# transponder-10_5_0.net
KiCad netlist of a schematic drawn in EAGLE
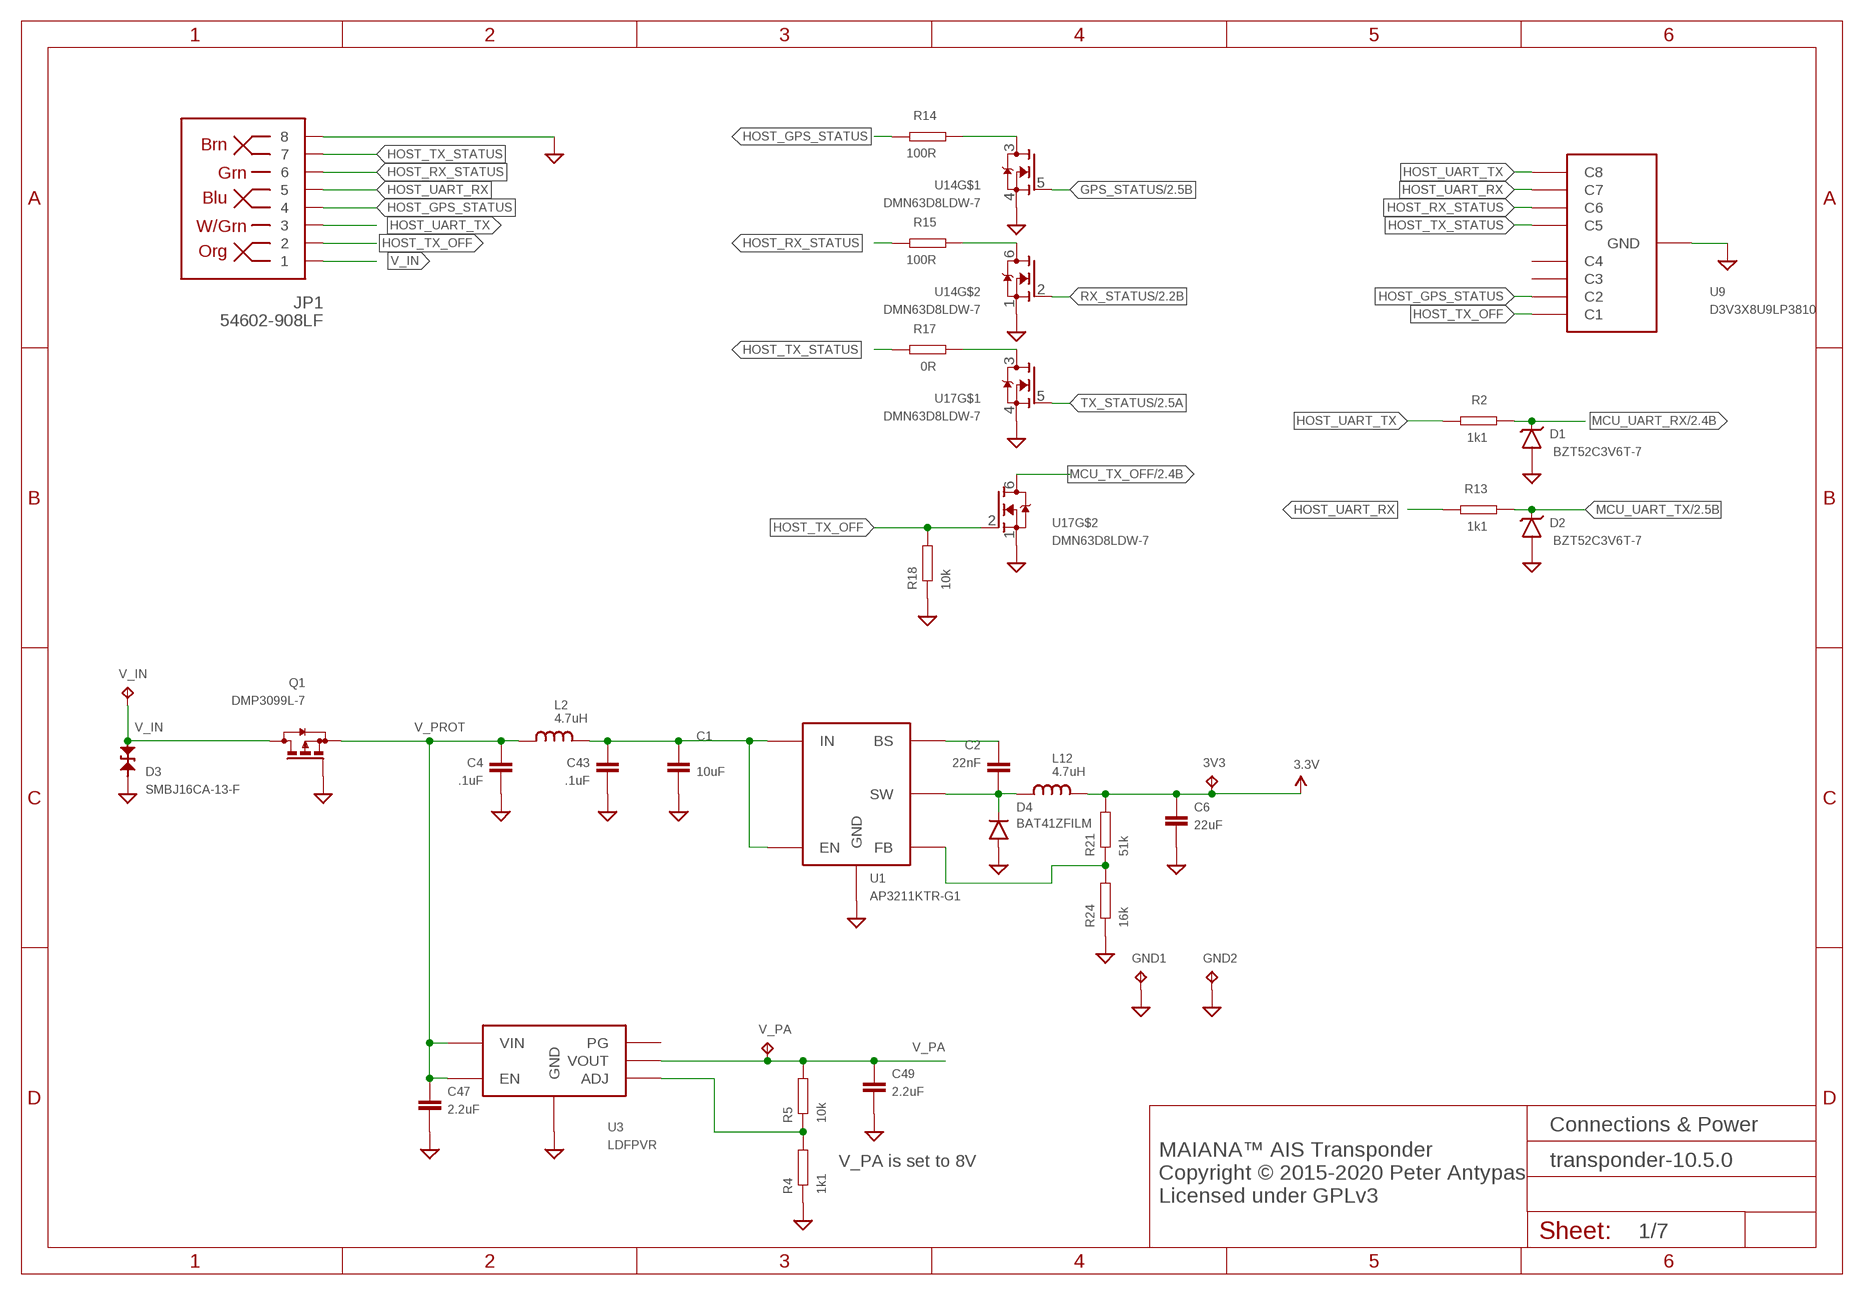
[diagram p0: schematic, sheet 1]
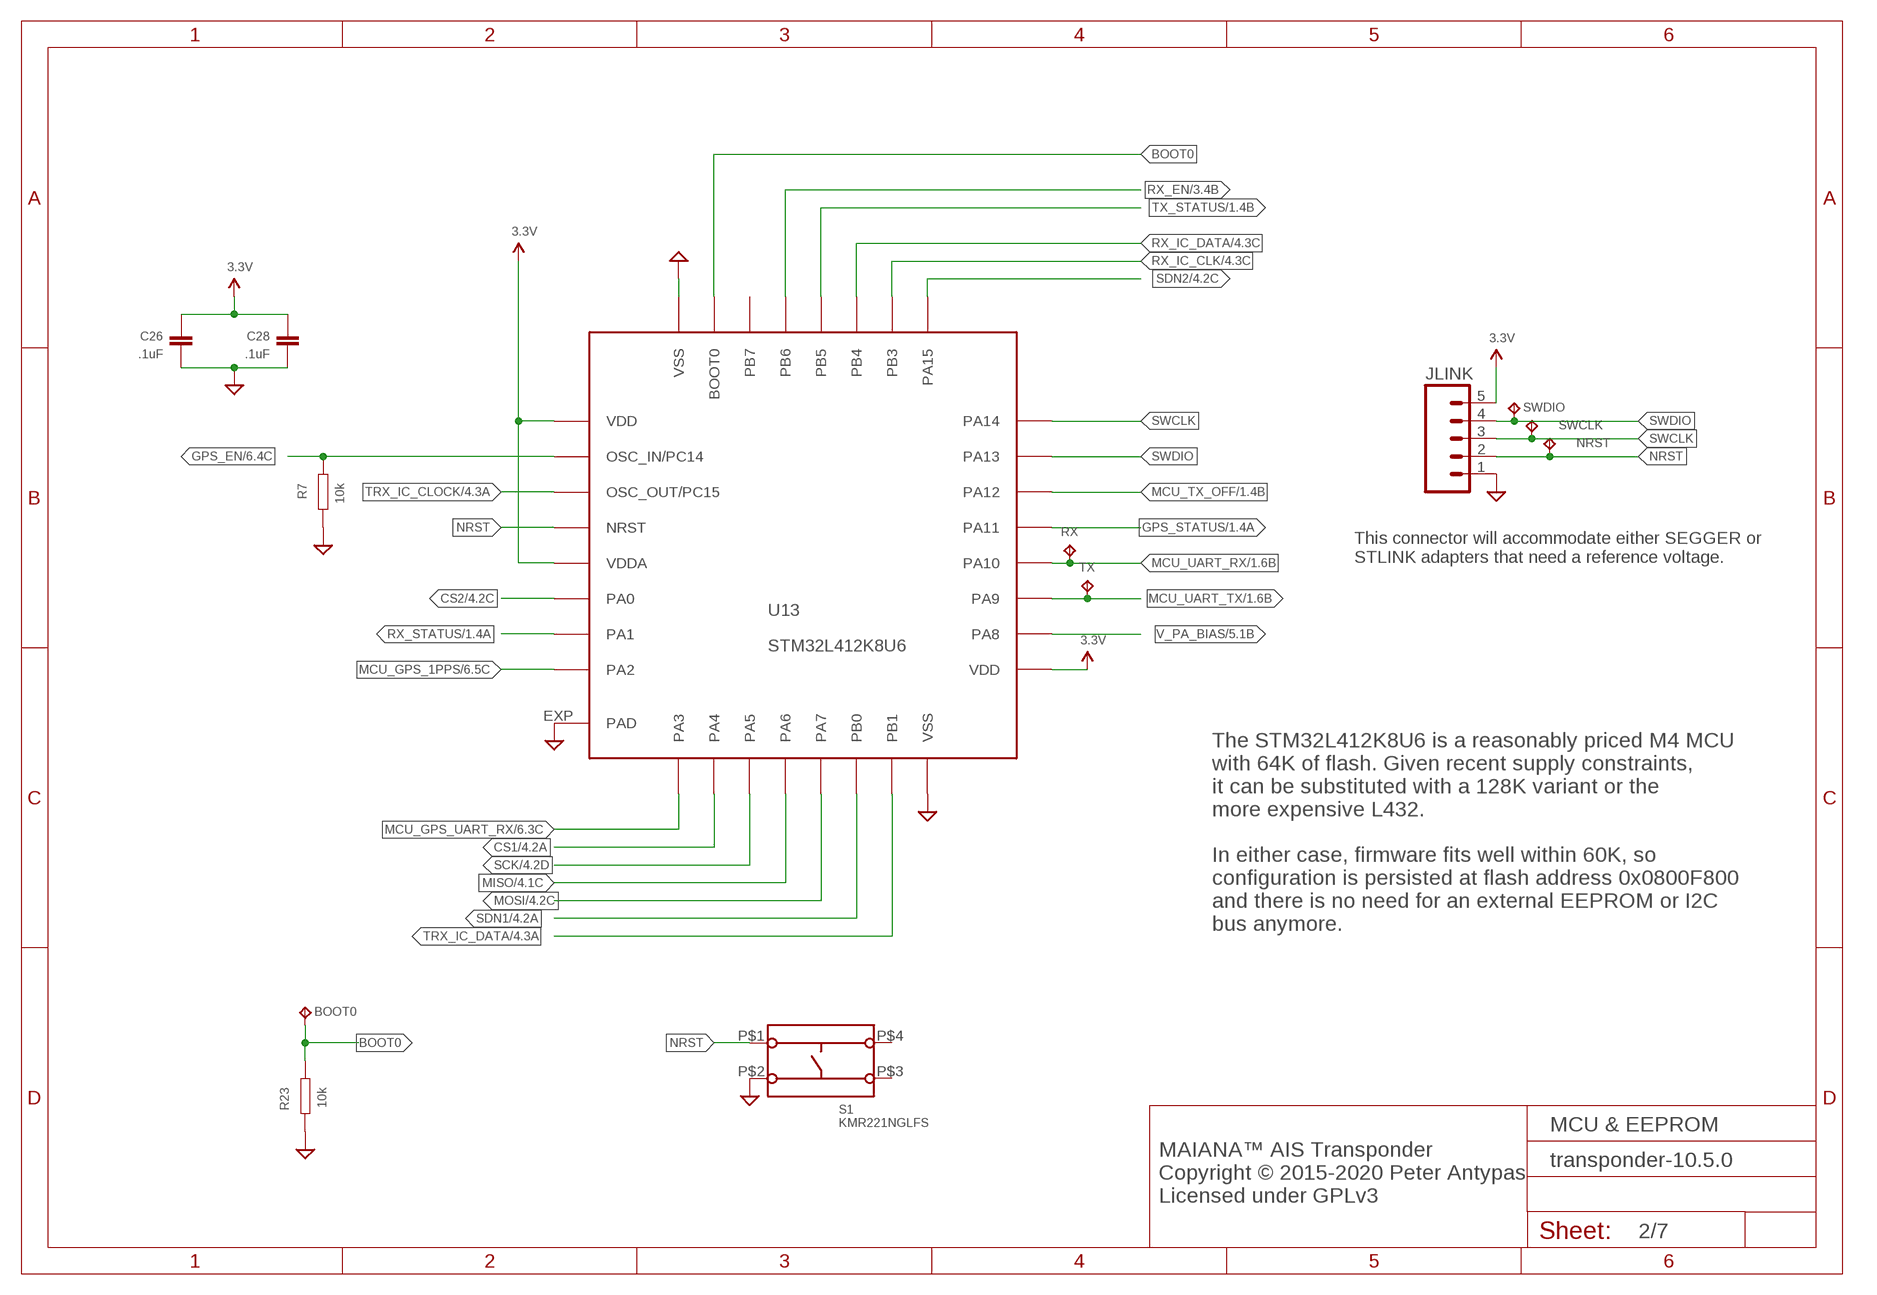
[diagram p1: schematic, sheet 2]
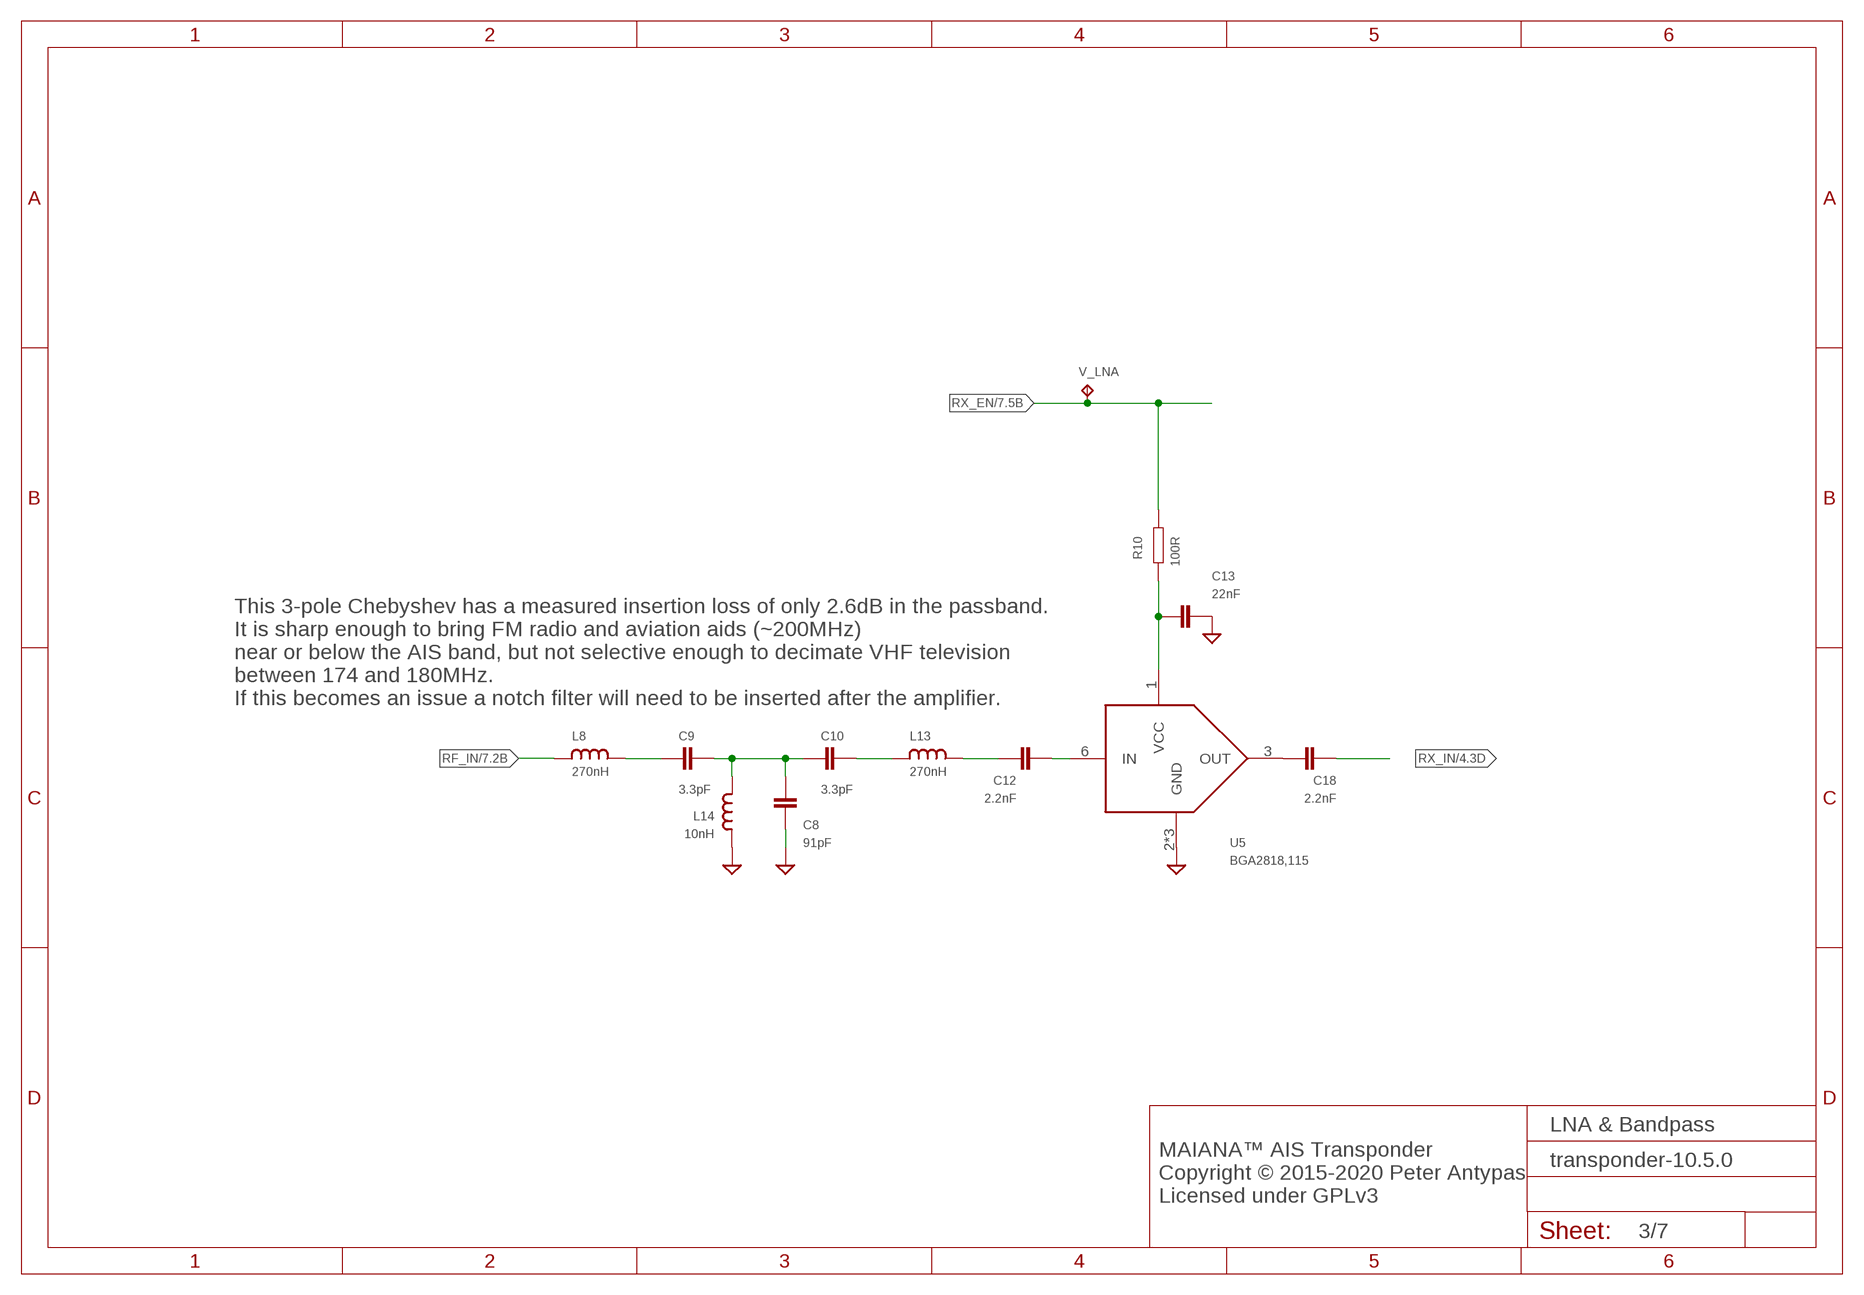
[diagram p2: schematic, sheet 3]
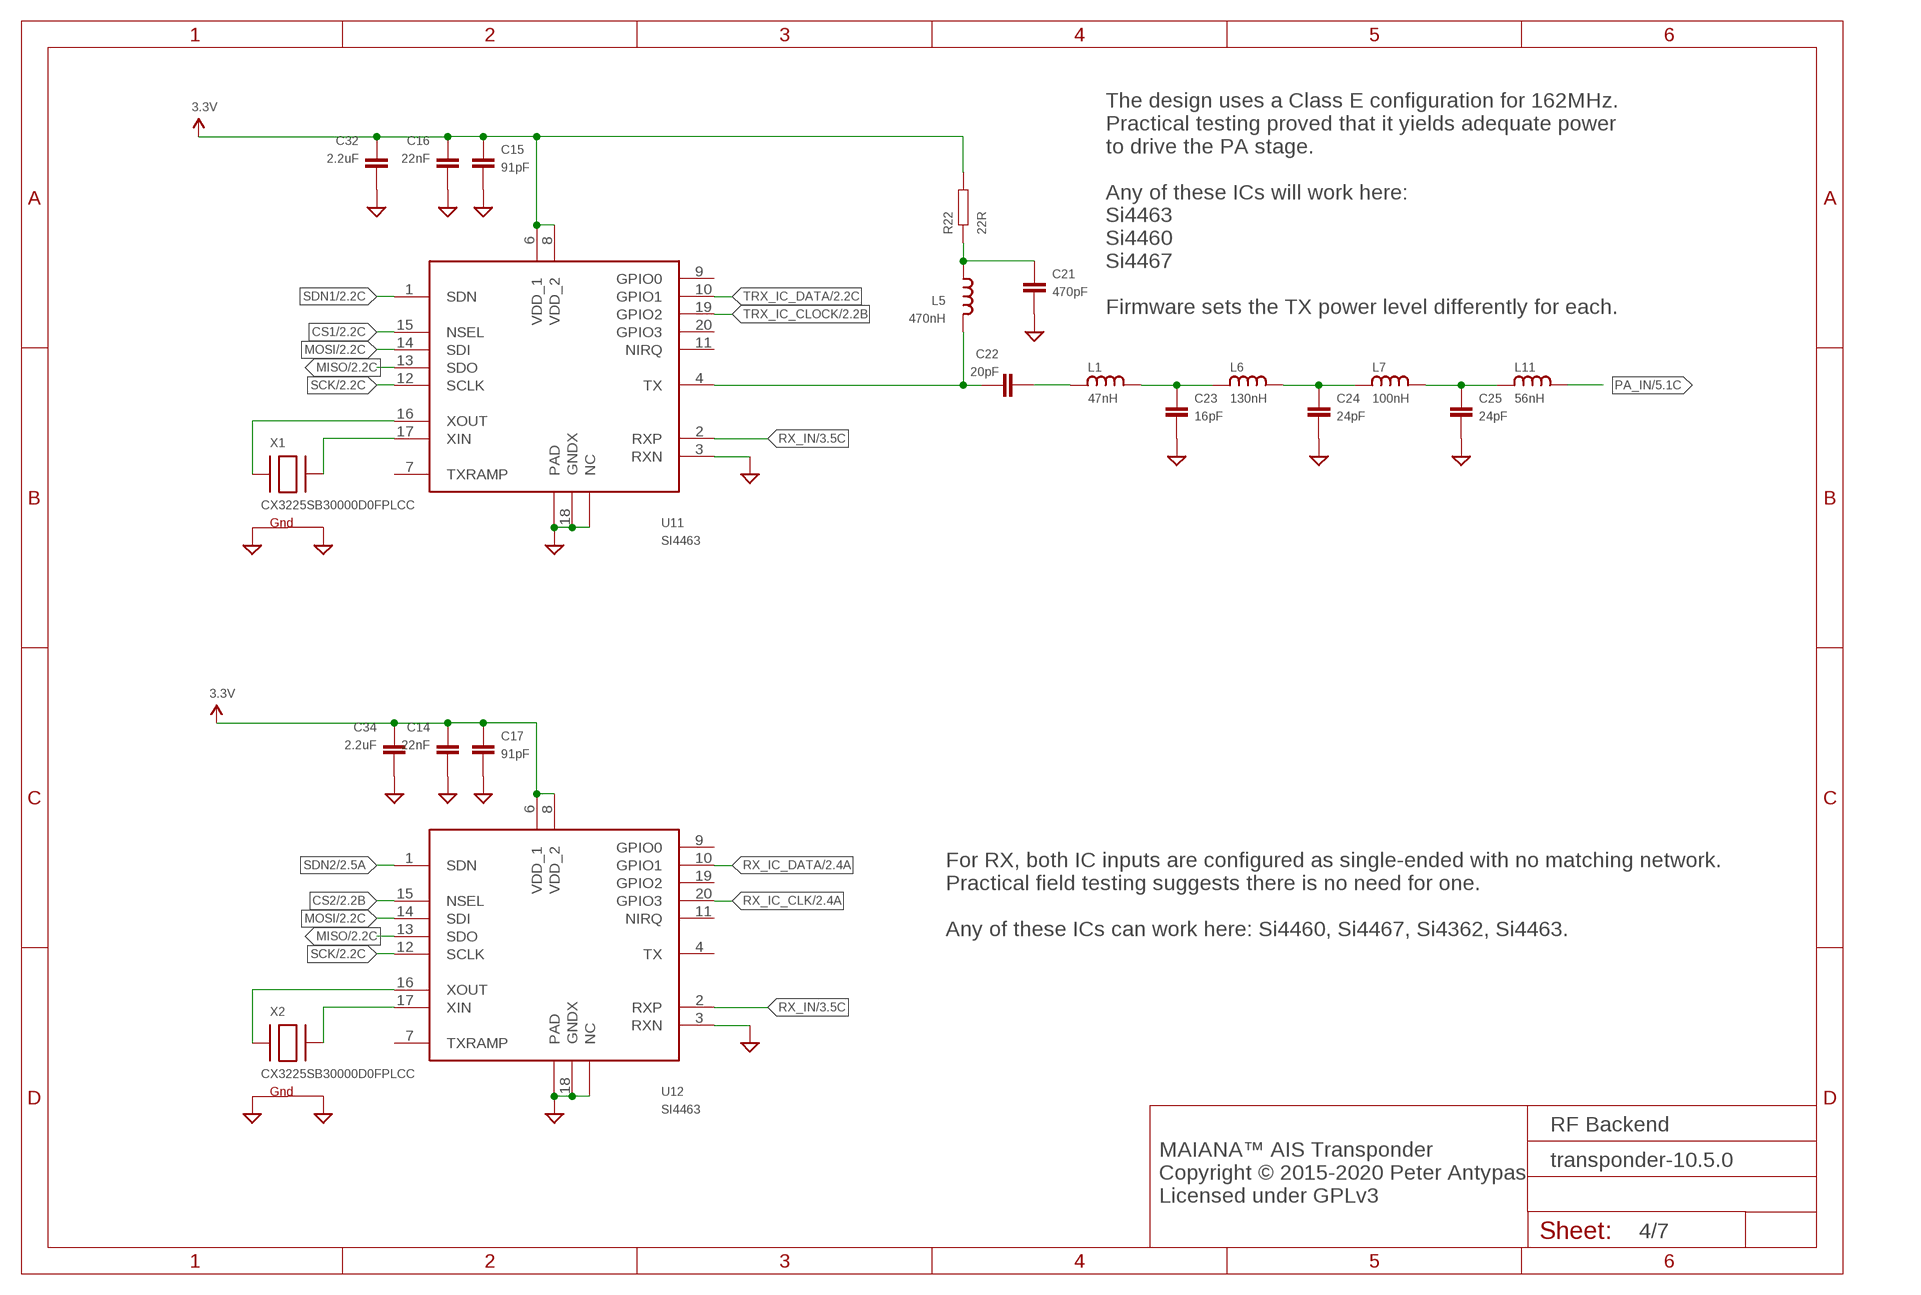
[diagram p3: schematic, sheet 4]
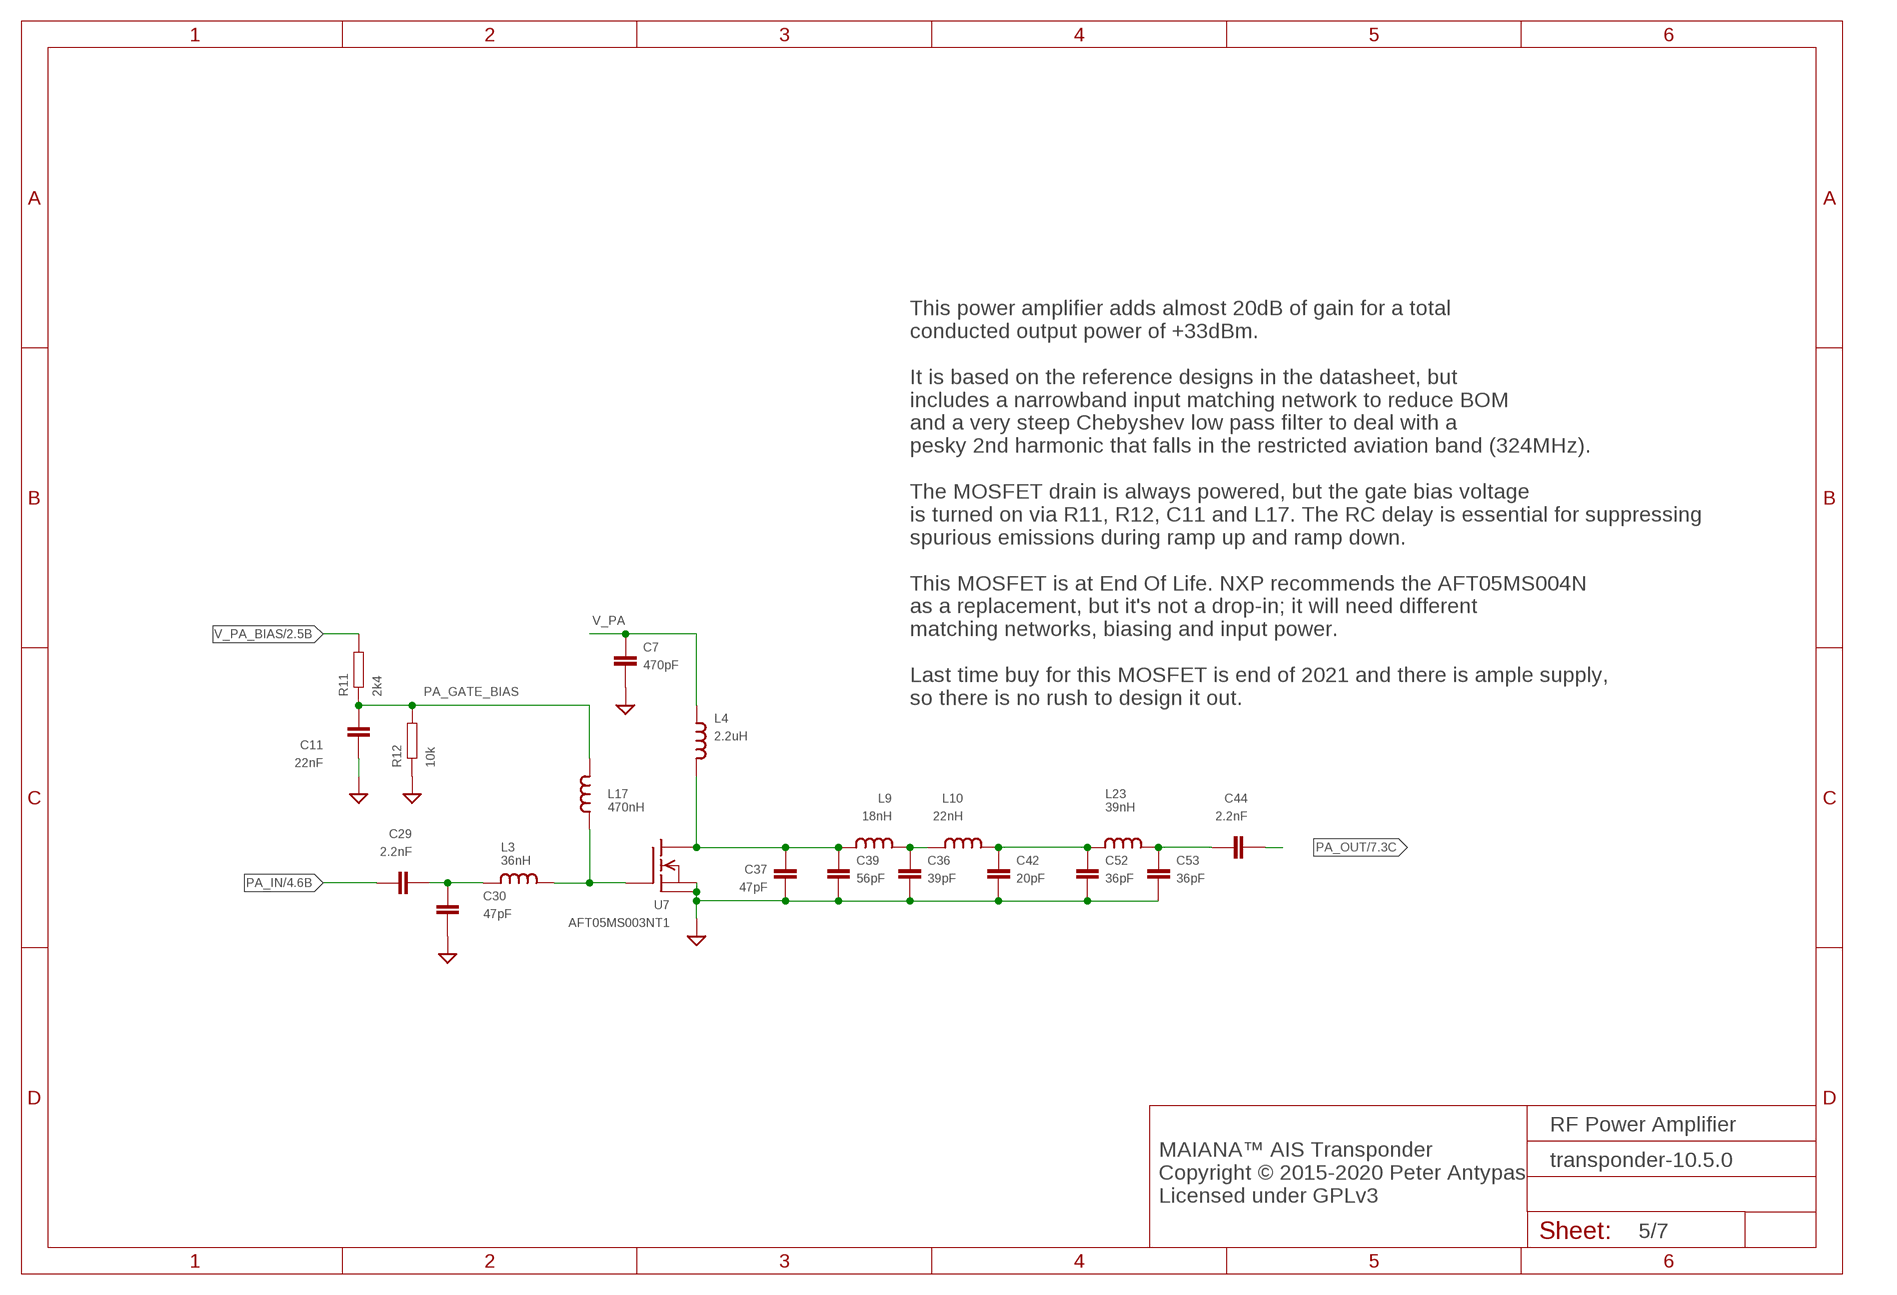
[diagram p4: schematic, sheet 5]
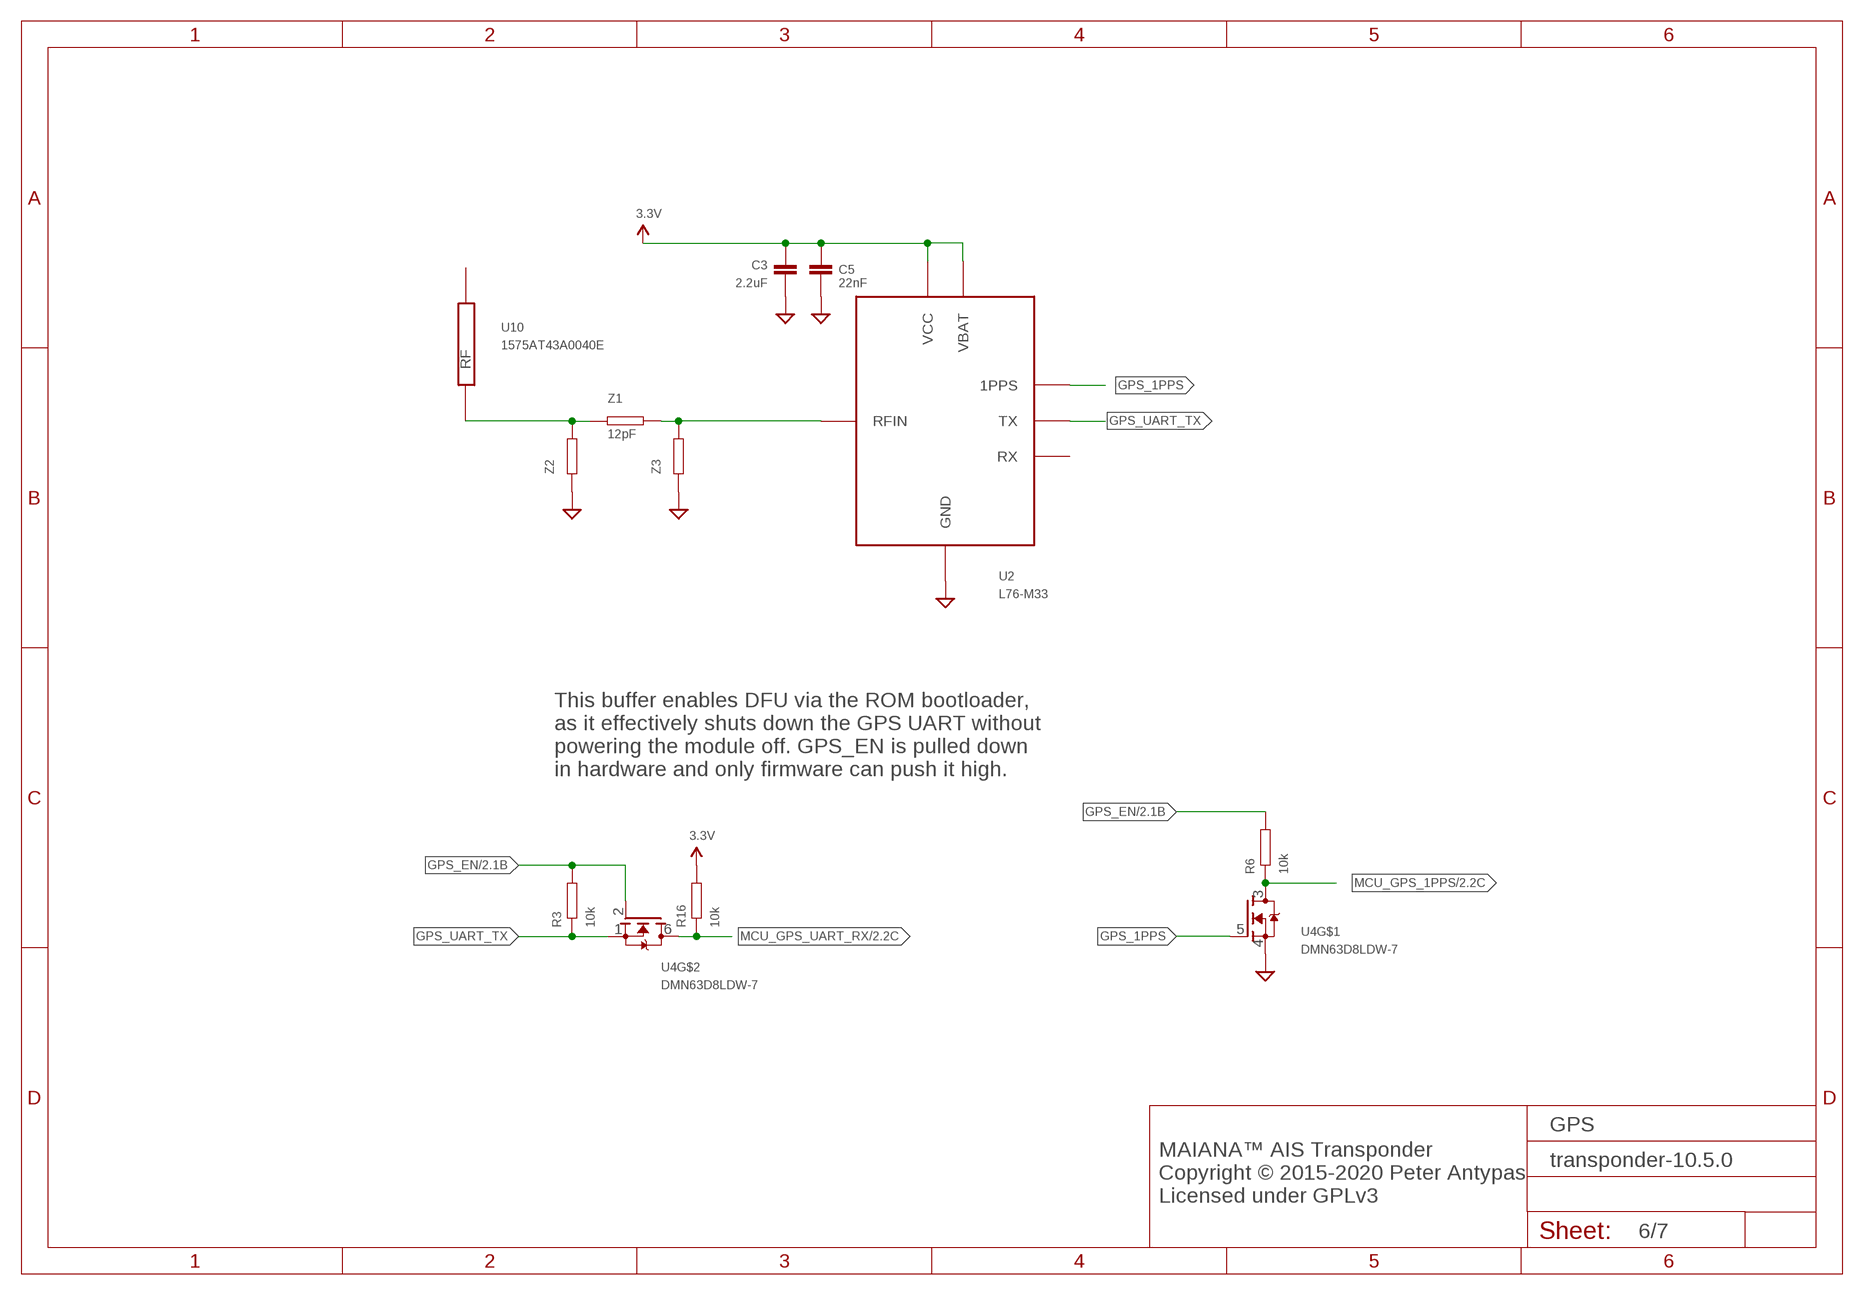
[diagram p5: schematic, sheet 6]
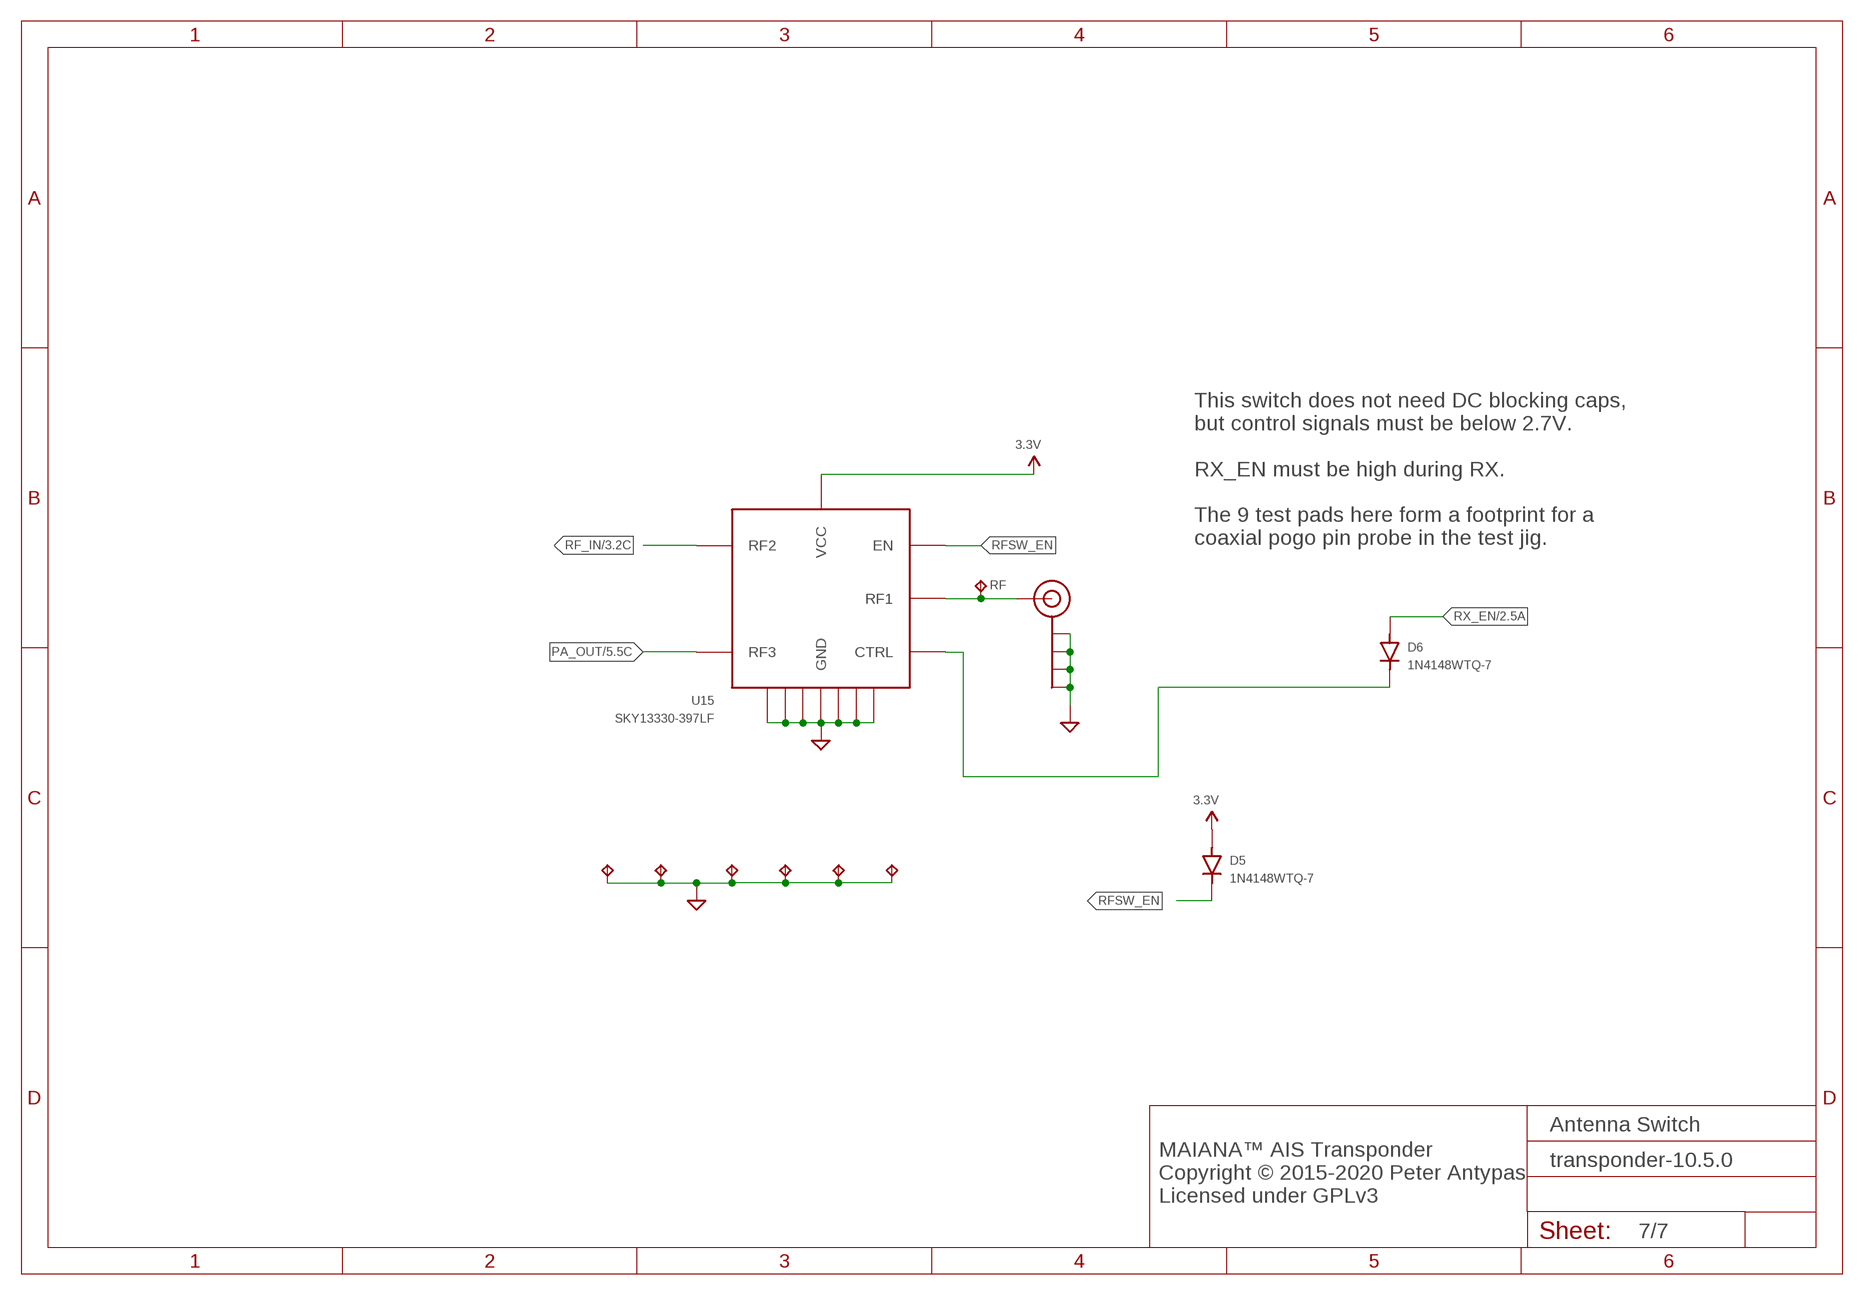
[diagram p6: schematic, sheet 7]

(export (version "E")
  (design (tool "Eeschema 10.0.6"))
  (components
    (comp (ref "BOOT0")
      (value "TPTP12R")
      (footprint "eagle-import:TP12R")
      (libsource (lib "eagle-import") (part "TPTP12R"))
    )
    (comp (ref "C26")
      (value ".1uF")
      (footprint "eagle-import:0603")
      (fields (field (name "PARTNO") "EMK107B7104KAHT"))
      (libsource (lib "eagle-import") (part "CAPACITOR0603"))
    )
    (comp (ref "C28")
      (value ".1uF")
      (footprint "eagle-import:0603")
      (fields (field (name "PARTNO") "EMK107B7104KAHT"))
      (libsource (lib "eagle-import") (part "CAPACITOR0603"))
    )
    (comp (ref "JLINK")
      (value "M05PTH")
      (footprint "eagle-import:1X05")
      (libsource (lib "eagle-import") (part "M05PTH"))
    )
    (comp (ref "NRST")
      (value "TPTP12R")
      (footprint "eagle-import:TP12R")
      (libsource (lib "eagle-import") (part "TPTP12R"))
    )
    (comp (ref "R7")
      (value "10k")
      (footprint "eagle-import:0603")
      (fields (field (name "PARTNO") "RC0603JR-0710KL"))
      (libsource (lib "eagle-import") (part "RESISTOR0603"))
    )
    (comp (ref "R23")
      (value "10k")
      (footprint "eagle-import:0603")
      (fields (field (name "PARTNO") "RC0603JR-0710KL"))
      (libsource (lib "eagle-import") (part "RESISTOR0603"))
    )
    (comp (ref "RX")
      (value "TPTP12R")
      (footprint "eagle-import:TP12R")
      (libsource (lib "eagle-import") (part "TPTP12R"))
    )
    (comp (ref "S1")
      (value "KMR221NGLFS")
      (footprint "eagle-import:KMR221NGLFS")
      (libsource (lib "eagle-import") (part "KMR221NGLFS"))
    )
    (comp (ref "SWCLK")
      (value "TPTP12R")
      (footprint "eagle-import:TP12R")
      (libsource (lib "eagle-import") (part "TPTP12R"))
    )
    (comp (ref "SWDIO")
      (value "TPTP12R")
      (footprint "eagle-import:TP12R")
      (libsource (lib "eagle-import") (part "TPTP12R"))
    )
    (comp (ref "TX")
      (value "TPTP12R")
      (footprint "eagle-import:TP12R")
      (libsource (lib "eagle-import") (part "TPTP12R"))
    )
    (comp (ref "U13")
      (value "STM32L412K8U6")
      (footprint "eagle-import:QFN32")
      (libsource (lib "eagle-import") (part "STM32L432KXXX"))
    )
    (comp (ref "C3")
      (value "2.2uF")
      (footprint "eagle-import:0603")
      (fields (field (name "PARTNO") "EMK107BJ225KA-T"))
      (libsource (lib "eagle-import") (part "CAPACITOR0603"))
    )
    (comp (ref "C5")
      (value "22nF")
      (footprint "eagle-import:0603")
      (fields (field (name "PARTNO") "GRM188R71E223KA01D"))
      (libsource (lib "eagle-import") (part "CAPACITOR0603"))
    )
    (comp (ref "R3")
      (value "10k")
      (footprint "eagle-import:0603")
      (fields (field (name "PARTNO") "RC0603JR-0710KL"))
      (libsource (lib "eagle-import") (part "RESISTOR0603"))
    )
    (comp (ref "R6")
      (value "10k")
      (footprint "eagle-import:0603")
      (fields (field (name "PARTNO") "RC0603JR-0710KL"))
      (libsource (lib "eagle-import") (part "RESISTOR0603"))
    )
    (comp (ref "R16")
      (value "10k")
      (footprint "eagle-import:0603")
      (fields (field (name "PARTNO") "RC0603JR-0710KL"))
      (libsource (lib "eagle-import") (part "RESISTOR0603"))
    )
    (comp (ref "U2")
      (value "L76-M33")
      (footprint "eagle-import:GPS_MODULE")
      (fields (field (name "PARTNO") "L70B-M39"))
      (libsource (lib "eagle-import") (part "L70"))
    )
    (comp (ref "U4")
      (value "DMN63D8LDW-7")
      (footprint "eagle-import:SOT363")
      (fields (field (name "PARTNO") "DMN63D8LDW-7"))
      (libsource (lib "eagle-import") (part "DMN63D8LDW"))
    )
    (comp (ref "U10")
      (value "1575AT43A0040E")
      (footprint "eagle-import:1575AT43A0040E")
      (libsource (lib "eagle-import") (part "1575AT43A0040E"))
    )
    (comp (ref "Z1")
      (value "12pF")
      (footprint "eagle-import:0603")
      (fields (field (name "PARTNO") "‎GRM1885C1H120GA01D‎"))
      (libsource (lib "eagle-import") (part "RESISTOR0603"))
    )
    (comp (ref "Z2")
      (value "RESISTOR0603")
      (footprint "eagle-import:0603")
      (fields (field (name "PARTNO") "*"))
      (libsource (lib "eagle-import") (part "RESISTOR0603"))
    )
    (comp (ref "Z3")
      (value "RESISTOR0603")
      (footprint "eagle-import:0603")
      (fields (field (name "PARTNO") "*"))
      (libsource (lib "eagle-import") (part "RESISTOR0603"))
    )
    (comp (ref "C7")
      (value "470pF")
      (footprint "eagle-import:0603")
      (fields (field (name "PARTNO") "GRM1885C1H471JA01D"))
      (libsource (lib "eagle-import") (part "CAPACITOR0603"))
    )
    (comp (ref "C11")
      (value "22nF")
      (footprint "eagle-import:0603")
      (fields (field (name "PARTNO") "GRM188R71E223KA01D"))
      (libsource (lib "eagle-import") (part "CAPACITOR0603"))
    )
    (comp (ref "C29")
      (value "2.2nF")
      (footprint "eagle-import:0603")
      (fields (field (name "PARTNO") "GRM1885C1H222JA01J"))
      (libsource (lib "eagle-import") (part "CAPACITOR0603"))
    )
    (comp (ref "C30")
      (value "47pF")
      (footprint "eagle-import:0603")
      (fields (field (name "PARTNO") "GRM1885C1H470JA01J"))
      (libsource (lib "eagle-import") (part "CAPACITOR0603"))
    )
    (comp (ref "C36")
      (value "39pF")
      (footprint "eagle-import:0603")
      (fields (field (name "PARTNO") "GRM1885C1H390JA01D"))
      (libsource (lib "eagle-import") (part "CAPACITOR0603"))
    )
    (comp (ref "C37")
      (value "47pF")
      (footprint "eagle-import:0603")
      (fields (field (name "PARTNO") "GRM1885C1H470JA01J"))
      (libsource (lib "eagle-import") (part "CAPACITOR0603"))
    )
    (comp (ref "C39")
      (value "56pF")
      (footprint "eagle-import:0603")
      (fields (field (name "PARTNO") "GRM1885C1H560JA01D"))
      (libsource (lib "eagle-import") (part "CAPACITOR0603"))
    )
    (comp (ref "C42")
      (value "20pF")
      (footprint "eagle-import:0603")
      (fields (field (name "PARTNO") "GRM1885C1H200JA01D"))
      (libsource (lib "eagle-import") (part "CAPACITOR0603"))
    )
    (comp (ref "C44")
      (value "2.2nF")
      (footprint "eagle-import:0603")
      (fields (field (name "PARTNO") "GRM1885C1H222JA01J"))
      (libsource (lib "eagle-import") (part "CAPACITOR0603"))
    )
    (comp (ref "C52")
      (value "36pF")
      (footprint "eagle-import:0603")
      (fields (field (name "PARTNO") "06035A360JAT2A"))
      (libsource (lib "eagle-import") (part "CAPACITOR0603"))
    )
    (comp (ref "C53")
      (value "36pF")
      (footprint "eagle-import:0603")
      (fields (field (name "PARTNO") "06035A360JAT2A"))
      (libsource (lib "eagle-import") (part "CAPACITOR0603"))
    )
    (comp (ref "L3")
      (value "36nH")
      (footprint "eagle-import:0603")
      (fields (field (name "PARTNO") "LQW18AN36NG00D"))
      (libsource (lib "eagle-import") (part "INDUCTOR0603"))
    )
    (comp (ref "L4")
      (value "2.2uH")
      (footprint "eagle-import:0805")
      (fields (field (name "PARTNO") "BRC2012T2R2MD"))
      (libsource (lib "eagle-import") (part "INDUCTOR0805"))
    )
    (comp (ref "L9")
      (value "18nH")
      (footprint "eagle-import:0603")
      (fields (field (name "PARTNO") "LQW18AN18NG00D"))
      (libsource (lib "eagle-import") (part "INDUCTOR0603"))
    )
    (comp (ref "L10")
      (value "22nH")
      (footprint "eagle-import:0603")
      (fields (field (name "PARTNO") "LQW18AN22NJ00D"))
      (libsource (lib "eagle-import") (part "INDUCTOR0603"))
    )
    (comp (ref "L17")
      (value "470nH")
      (footprint "eagle-import:0603")
      (fields (field (name "PARTNO") "HK1608R47J-T"))
      (libsource (lib "eagle-import") (part "INDUCTOR0603"))
    )
    (comp (ref "L23")
      (value "39nH")
      (footprint "eagle-import:0603")
      (fields (field (name "PARTNO") "LQW18AN39NG00D"))
      (libsource (lib "eagle-import") (part "INDUCTOR0603"))
    )
    (comp (ref "R11")
      (value "2k4")
      (footprint "eagle-import:0603")
      (fields (field (name "PARTNO") "RC0603FR-072K4L"))
      (libsource (lib "eagle-import") (part "RESISTOR0603"))
    )
    (comp (ref "R12")
      (value "10k")
      (footprint "eagle-import:0603")
      (fields (field (name "PARTNO") "RC0603JR-0710KL"))
      (libsource (lib "eagle-import") (part "RESISTOR0603"))
    )
    (comp (ref "U7")
      (value "AFT05MS003NT1")
      (footprint "eagle-import:SOT-89")
      (libsource (lib "eagle-import") (part "AFT0SMS003N"))
    )
    (comp (ref "C14")
      (value "22nF")
      (footprint "eagle-import:0603")
      (fields (field (name "PARTNO") "GRM188R71E223KA01D"))
      (libsource (lib "eagle-import") (part "CAPACITOR0603"))
    )
    (comp (ref "C15")
      (value "91pF")
      (footprint "eagle-import:0603")
      (fields (field (name "PARTNO") "GRM1885C2A910JA01D"))
      (libsource (lib "eagle-import") (part "CAPACITOR0603"))
    )
    (comp (ref "C16")
      (value "22nF")
      (footprint "eagle-import:0603")
      (fields (field (name "PARTNO") "GRM188R71E223KA01D"))
      (libsource (lib "eagle-import") (part "CAPACITOR0603"))
    )
    (comp (ref "C17")
      (value "91pF")
      (footprint "eagle-import:0603")
      (fields (field (name "PARTNO") "GRM1885C2A910JA01D"))
      (libsource (lib "eagle-import") (part "CAPACITOR0603"))
    )
    (comp (ref "C21")
      (value "470pF")
      (footprint "eagle-import:0603")
      (fields (field (name "PARTNO") "GRM1885C1H471JA01D"))
      (libsource (lib "eagle-import") (part "CAPACITOR0603"))
    )
    (comp (ref "C22")
      (value "20pF")
      (footprint "eagle-import:0603")
      (fields (field (name "PARTNO") "GRM1885C1H200JA01D"))
      (libsource (lib "eagle-import") (part "CAPACITOR0603"))
    )
    (comp (ref "C23")
      (value "16pF")
      (footprint "eagle-import:0603")
      (fields (field (name "PARTNO") "GCM1885C2A160JA16D"))
      (libsource (lib "eagle-import") (part "CAPACITOR0603"))
    )
    (comp (ref "C24")
      (value "24pF")
      (footprint "eagle-import:0603")
      (fields (field (name "PARTNO") "GRM1885C2A240JA01D"))
      (libsource (lib "eagle-import") (part "CAPACITOR0603"))
    )
    (comp (ref "C25")
      (value "24pF")
      (footprint "eagle-import:0603")
      (fields (field (name "PARTNO") "GRM1885C2A240JA01D"))
      (libsource (lib "eagle-import") (part "CAPACITOR0603"))
    )
    (comp (ref "C32")
      (value "2.2uF")
      (footprint "eagle-import:0603")
      (fields (field (name "PARTNO") "EMK107BJ225KA-T"))
      (libsource (lib "eagle-import") (part "CAPACITOR0603"))
    )
    (comp (ref "C34")
      (value "2.2uF")
      (footprint "eagle-import:0603")
      (fields (field (name "PARTNO") "EMK107BJ225KA-T"))
      (libsource (lib "eagle-import") (part "CAPACITOR0603"))
    )
    (comp (ref "L1")
      (value "47nH")
      (footprint "eagle-import:0603")
      (fields (field (name "PARTNO") "LQW18AN47NG00D"))
      (libsource (lib "eagle-import") (part "INDUCTOR0603"))
    )
    (comp (ref "L5")
      (value "470nH")
      (footprint "eagle-import:0603")
      (fields (field (name "PARTNO") "HK1608R47J-T"))
      (libsource (lib "eagle-import") (part "INDUCTOR0603"))
    )
    (comp (ref "L6")
      (value "130nH")
      (footprint "eagle-import:0603")
      (fields (field (name "PARTNO") "LQW18ANR13J00D"))
      (libsource (lib "eagle-import") (part "INDUCTOR0603"))
    )
    (comp (ref "L7")
      (value "100nH")
      (footprint "eagle-import:0603")
      (fields (field (name "PARTNO") "LQW18ANR10G00D"))
      (libsource (lib "eagle-import") (part "INDUCTOR0603"))
    )
    (comp (ref "L11")
      (value "56nH")
      (footprint "eagle-import:0603")
      (fields (field (name "PARTNO") "LQW18AN56NG00D"))
      (libsource (lib "eagle-import") (part "INDUCTOR0603"))
    )
    (comp (ref "R22")
      (value "22R")
      (footprint "eagle-import:0603")
      (fields (field (name "PARTNO") "RC0603JR-0722RL"))
      (libsource (lib "eagle-import") (part "RESISTOR0603"))
    )
    (comp (ref "U11")
      (value "SI4463")
      (footprint "eagle-import:SI4463")
      (fields (field (name "PARTNO") "SI4463-C2A-GMR"))
      (libsource (lib "eagle-import") (part "SI4463"))
    )
    (comp (ref "U12")
      (value "SI4463")
      (footprint "eagle-import:SI4463")
      (fields (field (name "PARTNO") "SI4463-C2A-GMR"))
      (libsource (lib "eagle-import") (part "SI4463"))
    )
    (comp (ref "X1")
      (value "CX3225SB30000D0FPLCC")
      (footprint "eagle-import:NX3225")
      (libsource (lib "eagle-import") (part "XTAL-4-3225"))
    )
    (comp (ref "X2")
      (value "CX3225SB30000D0FPLCC")
      (footprint "eagle-import:NX3225")
      (libsource (lib "eagle-import") (part "XTAL-4-3225"))
    )
    (comp (ref "3V3")
      (value "TPTP12R")
      (footprint "eagle-import:TP12R")
      (libsource (lib "eagle-import") (part "TPTP12R"))
    )
    (comp (ref "C1")
      (value "10uF")
      (footprint "eagle-import:0805")
      (fields (field (name "PARTNO") "EMK212ABJ106KG-T"))
      (libsource (lib "eagle-import") (part "CAPACITOR0805"))
    )
    (comp (ref "C2")
      (value "22nF")
      (footprint "eagle-import:0603")
      (fields (field (name "PARTNO") "GRM188R71E223KA01D"))
      (libsource (lib "eagle-import") (part "CAPACITOR0603"))
    )
    (comp (ref "C4")
      (value ".1uF")
      (footprint "eagle-import:0603")
      (fields (field (name "PARTNO") "EMK107B7104KAHT"))
      (libsource (lib "eagle-import") (part "CAPACITOR0603"))
    )
    (comp (ref "C6")
      (value "22uF")
      (footprint "eagle-import:0805")
      (libsource (lib "eagle-import") (part "CAPACITOR0805"))
    )
    (comp (ref "C43")
      (value ".1uF")
      (footprint "eagle-import:0603")
      (fields (field (name "PARTNO") "EMK107B7104KAHT"))
      (libsource (lib "eagle-import") (part "CAPACITOR0603"))
    )
    (comp (ref "C47")
      (value "2.2uF")
      (footprint "eagle-import:0603")
      (fields (field (name "PARTNO") "EMK107BJ225KA-T"))
      (libsource (lib "eagle-import") (part "CAPACITOR0603"))
    )
    (comp (ref "C49")
      (value "2.2uF")
      (footprint "eagle-import:0603")
      (fields (field (name "PARTNO") "EMK107BJ225KA-T"))
      (libsource (lib "eagle-import") (part "CAPACITOR0603"))
    )
    (comp (ref "D1")
      (value "BZT52C3V6T-7")
      (footprint "eagle-import:SOD523")
      (libsource (lib "eagle-import") (part "DIODE-ZENERSOD523"))
    )
    (comp (ref "D2")
      (value "BZT52C3V6T-7")
      (footprint "eagle-import:SOD523")
      (libsource (lib "eagle-import") (part "DIODE-ZENERSOD523"))
    )
    (comp (ref "D3")
      (value "SMBJ16CA-13-F")
      (footprint "eagle-import:SMB-BIDIR")
      (fields (field (name "PARTNO") "SMBJ16CA-13-F"))
      (libsource (lib "eagle-import") (part "DIODE-TVS-BIDIRSMB"))
    )
    (comp (ref "D4")
      (value "BAT41ZFILM")
      (footprint "eagle-import:SOD-323")
      (libsource (lib "eagle-import") (part "DIODEBAS16"))
    )
    (comp (ref "GND1")
      (value "TPTP12R")
      (footprint "eagle-import:TP12R")
      (libsource (lib "eagle-import") (part "TPTP12R"))
    )
    (comp (ref "GND2")
      (value "TPTP12R")
      (footprint "eagle-import:TP12R")
      (libsource (lib "eagle-import") (part "TPTP12R"))
    )
    (comp (ref "JP1")
      (value "54602-908LF")
      (footprint "eagle-import:RJ45-8")
      (fields (field (name "PARTNO") "54602-908LF‎"))
      (libsource (lib "eagle-import") (part "RJ45-8PTH"))
    )
    (comp (ref "L2")
      (value "4.7uH")
      (footprint "eagle-import:0805")
      (fields (field (name "PARTNO") "MLZ2012M4R7WT000"))
      (libsource (lib "eagle-import") (part "INDUCTOR0805"))
    )
    (comp (ref "L12")
      (value "4.7uH")
      (footprint "eagle-import:0805")
      (fields (field (name "PARTNO") "MLZ2012M4R7WT000"))
      (libsource (lib "eagle-import") (part "INDUCTOR0805"))
    )
    (comp (ref "Q1")
      (value "DMP3099L-7")
      (footprint "eagle-import:SOT23")
      (libsource (lib "eagle-import") (part "BSS84"))
    )
    (comp (ref "R2")
      (value "1k1")
      (footprint "eagle-import:0603")
      (fields (field (name "PARTNO") "RC0603JR-071K1L"))
      (libsource (lib "eagle-import") (part "RESISTOR0603"))
    )
    (comp (ref "R4")
      (value "1k1")
      (footprint "eagle-import:0603")
      (fields (field (name "PARTNO") "RC0603JR-071K1L"))
      (libsource (lib "eagle-import") (part "RESISTOR0603"))
    )
    (comp (ref "R5")
      (value "10k")
      (footprint "eagle-import:0603")
      (fields (field (name "PARTNO") "RC0603JR-0710KL"))
      (libsource (lib "eagle-import") (part "RESISTOR0603"))
    )
    (comp (ref "R13")
      (value "1k1")
      (footprint "eagle-import:0603")
      (fields (field (name "PARTNO") "RC0603JR-071K1L"))
      (libsource (lib "eagle-import") (part "RESISTOR0603"))
    )
    (comp (ref "R14")
      (value "100R")
      (footprint "eagle-import:0603")
      (fields (field (name "PARTNO") "RC0603JR-07100RL"))
      (libsource (lib "eagle-import") (part "RESISTOR0603"))
    )
    (comp (ref "R15")
      (value "100R")
      (footprint "eagle-import:0603")
      (fields (field (name "PARTNO") "RC0603JR-07100RL"))
      (libsource (lib "eagle-import") (part "RESISTOR0603"))
    )
    (comp (ref "R17")
      (value "0R")
      (footprint "eagle-import:0603")
      (fields (field (name "PARTNO") "RC0603JR-070RL"))
      (libsource (lib "eagle-import") (part "RESISTOR0603"))
    )
    (comp (ref "R18")
      (value "10k")
      (footprint "eagle-import:0603")
      (fields (field (name "PARTNO") "RC0603JR-0710KL"))
      (libsource (lib "eagle-import") (part "RESISTOR0603"))
    )
    (comp (ref "R21")
      (value "51k")
      (footprint "eagle-import:0603")
      (fields (field (name "PARTNO") "RC0603JR-0751KL"))
      (libsource (lib "eagle-import") (part "RESISTOR0603"))
    )
    (comp (ref "R24")
      (value "16k")
      (footprint "eagle-import:0603")
      (fields (field (name "PARTNO") "RC0603FR-1016KL"))
      (libsource (lib "eagle-import") (part "RESISTOR0603"))
    )
    (comp (ref "U1")
      (value "AP3211KTR-G1")
      (footprint "eagle-import:SOT23-6")
      (libsource (lib "eagle-import") (part "AP3211"))
    )
    (comp (ref "U3")
      (value "LDFPVR")
      (footprint "eagle-import:DFN6-2X2")
      (fields (field (name "PARTNO") "LDFPUR"))
      (libsource (lib "eagle-import") (part "LDFPVR"))
    )
    (comp (ref "U9")
      (value "D3V3X8U9LP3810")
      (footprint "eagle-import:U-DFN3810-9(B)")
      (libsource (lib "eagle-import") (part "D3V3X8U9LP3810"))
    )
    (comp (ref "U14")
      (value "DMN63D8LDW-7")
      (footprint "eagle-import:SOT363")
      (fields (field (name "PARTNO") "DMN63D8LDW-7"))
      (libsource (lib "eagle-import") (part "DMN63D8LDW"))
    )
    (comp (ref "U17")
      (value "DMN63D8LDW-7")
      (footprint "eagle-import:SOT363")
      (fields (field (name "PARTNO") "DMN63D8LDW-7"))
      (libsource (lib "eagle-import") (part "DMN63D8LDW"))
    )
    (comp (ref "V_IN")
      (value "TPTP12R")
      (footprint "eagle-import:TP12R")
      (libsource (lib "eagle-import") (part "TPTP12R"))
    )
    (comp (ref "V_PA")
      (value "TPTP12R")
      (footprint "eagle-import:TP12R")
      (libsource (lib "eagle-import") (part "TPTP12R"))
    )
    (comp (ref "C8")
      (value "91pF")
      (footprint "eagle-import:0603")
      (fields (field (name "PARTNO") "GRM1885C2A910JA01D"))
      (libsource (lib "eagle-import") (part "CAPACITOR0603"))
    )
    (comp (ref "C9")
      (value "3.3pF")
      (footprint "eagle-import:0603")
      (fields (field (name "PARTNO") "GRM1885C1H3R3BA01D"))
      (libsource (lib "eagle-import") (part "CAPACITOR0603"))
    )
    (comp (ref "C10")
      (value "3.3pF")
      (footprint "eagle-import:0603")
      (fields (field (name "PARTNO") "GRM1885C1H3R3BA01D"))
      (libsource (lib "eagle-import") (part "CAPACITOR0603"))
    )
    (comp (ref "C12")
      (value "2.2nF")
      (footprint "eagle-import:0603")
      (fields (field (name "PARTNO") "GRM1885C1H222JA01J"))
      (libsource (lib "eagle-import") (part "CAPACITOR0603"))
    )
    (comp (ref "C13")
      (value "22nF")
      (footprint "eagle-import:0603")
      (fields (field (name "PARTNO") "GRM188R71E223KA01D"))
      (libsource (lib "eagle-import") (part "CAPACITOR0603"))
    )
    (comp (ref "C18")
      (value "2.2nF")
      (footprint "eagle-import:0603")
      (fields (field (name "PARTNO") "GRM1885C1H222JA01J"))
      (libsource (lib "eagle-import") (part "CAPACITOR0603"))
    )
    (comp (ref "L8")
      (value "270nH")
      (footprint "eagle-import:0603")
      (fields (field (name "PARTNO") "LQW18ANR27J00D"))
      (libsource (lib "eagle-import") (part "INDUCTOR0603"))
    )
    (comp (ref "L13")
      (value "270nH")
      (footprint "eagle-import:0603")
      (fields (field (name "PARTNO") "LQW18ANR27J00D"))
      (libsource (lib "eagle-import") (part "INDUCTOR0603"))
    )
    (comp (ref "L14")
      (value "10nH")
      (footprint "eagle-import:0603")
      (fields (field (name "PARTNO") "LQW18AN10NG00D"))
      (libsource (lib "eagle-import") (part "INDUCTOR0603"))
    )
    (comp (ref "R10")
      (value "100R")
      (footprint "eagle-import:0603")
      (fields (field (name "PARTNO") "RC0603JR-07100RL"))
      (libsource (lib "eagle-import") (part "RESISTOR0603"))
    )
    (comp (ref "U5")
      (value "BGA2818,115")
      (footprint "eagle-import:SOT363")
      (libsource (lib "eagle-import") (part "BGA2870"))
    )
    (comp (ref "V_LNA")
      (value "TPTP12R")
      (footprint "eagle-import:TP12R")
      (libsource (lib "eagle-import") (part "TPTP12R"))
    )
    (comp (ref "D5")
      (value "1N4148WTQ-7")
      (footprint "eagle-import:SOD523")
      (fields (field (name "PARTNO") "*"))
      (libsource (lib "eagle-import") (part "DIODE-SILICONSOD523"))
    )
    (comp (ref "D6")
      (value "1N4148WTQ-7")
      (footprint "eagle-import:SOD523")
      (fields (field (name "PARTNO") "*"))
      (libsource (lib "eagle-import") (part "DIODE-SILICONSOD523"))
    )
    (comp (ref "J$1")
      (value "SMA_EDGE")
      (footprint "eagle-import:SMA-EDGE")
      (libsource (lib "eagle-import") (part "SMA_EDGE"))
    )
    (comp (ref "RF")
      (value "TPTP10R")
      (footprint "eagle-import:TP10R")
      (libsource (lib "eagle-import") (part "TPTP10R"))
    )
    (comp (ref "SWDIO1")
      (value "TPTP12R")
      (footprint "eagle-import:TP12R")
      (libsource (lib "eagle-import") (part "TPTP12R"))
    )
    (comp (ref "SWDIO2")
      (value "TPTP12R")
      (footprint "eagle-import:TP12R")
      (libsource (lib "eagle-import") (part "TPTP12R"))
    )
    (comp (ref "SWDIO3")
      (value "TPTP12R")
      (footprint "eagle-import:TP12R")
      (libsource (lib "eagle-import") (part "TPTP12R"))
    )
    (comp (ref "SWDIO4")
      (value "TPTP12R")
      (footprint "eagle-import:TP12R")
      (libsource (lib "eagle-import") (part "TPTP12R"))
    )
    (comp (ref "SWDIO5")
      (value "TPTP12R")
      (footprint "eagle-import:TP12R")
      (libsource (lib "eagle-import") (part "TPTP12R"))
    )
    (comp (ref "SWDIO6")
      (value "TPTP12R")
      (footprint "eagle-import:TP12R")
      (libsource (lib "eagle-import") (part "TPTP12R"))
    )
    (comp (ref "U15")
      (value "SKY13330-397LF")
      (footprint "eagle-import:QFN12")
      (libsource (lib "eagle-import") (part "SKYWORKS-13330397LF"))
    )
  )
  (nets
    (net (code "1") (name "3.3V") (class "Default")
      (node (ref "3V3") (pin "TP") (pinfunction "TP_TP") (pintype "input"))
      (node (ref "C14") (pin "P$1") (pinfunction "1_P$1") (pintype "passive"))
      (node (ref "C15") (pin "P$1") (pinfunction "1_P$1") (pintype "passive"))
      (node (ref "C16") (pin "P$1") (pinfunction "1_P$1") (pintype "passive"))
      (node (ref "C17") (pin "P$1") (pinfunction "1_P$1") (pintype "passive"))
      (node (ref "C26") (pin "P$1") (pinfunction "1_P$1") (pintype "passive"))
      (node (ref "C28") (pin "P$1") (pinfunction "1_P$1") (pintype "passive"))
      (node (ref "C3") (pin "P$1") (pinfunction "1_P$1") (pintype "passive"))
      (node (ref "C32") (pin "P$1") (pinfunction "1_P$1") (pintype "passive"))
      (node (ref "C34") (pin "P$1") (pinfunction "1_P$1") (pintype "passive"))
      (node (ref "C5") (pin "P$1") (pinfunction "1_P$1") (pintype "passive"))
      (node (ref "C6") (pin "P$1") (pinfunction "1_P$1") (pintype "passive"))
      (node (ref "D5") (pin "A") (pinfunction "A_A") (pintype "bidirectional"))
      (node (ref "JLINK") (pin "5") (pinfunction "5_5") (pintype "passive"))
      (node (ref "L12") (pin "P$2") (pinfunction "2_P$2") (pintype "passive"))
      (node (ref "R16") (pin "P$2") (pinfunction "P$2_P$2") (pintype "passive"))
      (node (ref "R21") (pin "P$2") (pinfunction "P$2_P$2") (pintype "passive"))
      (node (ref "R22") (pin "P$2") (pinfunction "P$2_P$2") (pintype "passive"))
      (node (ref "U11") (pin "6") (pinfunction "VDD_1_6") (pintype "power_in"))
      (node (ref "U11") (pin "8") (pinfunction "VDD_2_8") (pintype "power_in"))
      (node (ref "U12") (pin "6") (pinfunction "VDD_1_6") (pintype "power_in"))
      (node (ref "U12") (pin "8") (pinfunction "VDD_2_8") (pintype "power_in"))
      (node (ref "U13") (pin "1") (pinfunction "VDD_1") (pintype "bidirectional"))
      (node (ref "U13") (pin "17") (pinfunction "VDD_17") (pintype "bidirectional"))
      (node (ref "U13") (pin "5") (pinfunction "VDDA_5") (pintype "bidirectional"))
      (node (ref "U15") (pin "P$9") (pinfunction "VCC_P$9") (pintype "bidirectional"))
      (node (ref "U2") (pin "P$6") (pinfunction "VBAT_P$6") (pintype "bidirectional"))
      (node (ref "U2") (pin "P$8") (pinfunction "VCC_P$8") (pintype "bidirectional"))
    )
    (net (code "2") (name "BOOT0") (class "Default")
      (node (ref "BOOT0") (pin "TP") (pinfunction "TP_TP") (pintype "input"))
      (node (ref "R23") (pin "P$1") (pinfunction "P$1_P$1") (pintype "passive"))
      (node (ref "U13") (pin "31") (pinfunction "BOOT0_31") (pintype "bidirectional"))
    )
    (net (code "3") (name "CS1") (class "Default")
      (node (ref "U11") (pin "15") (pinfunction "NSEL_15") (pintype "input"))
      (node (ref "U13") (pin "10") (pinfunction "PA4_10") (pintype "bidirectional"))
    )
    (net (code "4") (name "CS2") (class "Default")
      (node (ref "U12") (pin "15") (pinfunction "NSEL_15") (pintype "input"))
      (node (ref "U13") (pin "6") (pinfunction "PA0_6") (pintype "bidirectional"))
    )
    (net (code "5") (name "GND") (class "Default")
      (node (ref "C1") (pin "P$2") (pinfunction "2_P$2") (pintype "passive"))
      (node (ref "C11") (pin "P$2") (pinfunction "2_P$2") (pintype "passive"))
      (node (ref "C13") (pin "P$2") (pinfunction "2_P$2") (pintype "passive"))
      (node (ref "C14") (pin "P$2") (pinfunction "2_P$2") (pintype "passive"))
      (node (ref "C15") (pin "P$2") (pinfunction "2_P$2") (pintype "passive"))
      (node (ref "C16") (pin "P$2") (pinfunction "2_P$2") (pintype "passive"))
      (node (ref "C17") (pin "P$2") (pinfunction "2_P$2") (pintype "passive"))
      (node (ref "C21") (pin "P$2") (pinfunction "2_P$2") (pintype "passive"))
      (node (ref "C23") (pin "P$2") (pinfunction "2_P$2") (pintype "passive"))
      (node (ref "C24") (pin "P$2") (pinfunction "2_P$2") (pintype "passive"))
      (node (ref "C25") (pin "P$2") (pinfunction "2_P$2") (pintype "passive"))
      (node (ref "C26") (pin "P$2") (pinfunction "2_P$2") (pintype "passive"))
      (node (ref "C28") (pin "P$2") (pinfunction "2_P$2") (pintype "passive"))
      (node (ref "C3") (pin "P$2") (pinfunction "2_P$2") (pintype "passive"))
      (node (ref "C30") (pin "P$2") (pinfunction "2_P$2") (pintype "passive"))
      (node (ref "C32") (pin "P$2") (pinfunction "2_P$2") (pintype "passive"))
      (node (ref "C34") (pin "P$2") (pinfunction "2_P$2") (pintype "passive"))
      (node (ref "C36") (pin "P$2") (pinfunction "2_P$2") (pintype "passive"))
      (node (ref "C37") (pin "P$2") (pinfunction "2_P$2") (pintype "passive"))
      (node (ref "C39") (pin "P$2") (pinfunction "2_P$2") (pintype "passive"))
      (node (ref "C4") (pin "P$2") (pinfunction "2_P$2") (pintype "passive"))
      (node (ref "C42") (pin "P$2") (pinfunction "2_P$2") (pintype "passive"))
      (node (ref "C43") (pin "P$2") (pinfunction "2_P$2") (pintype "passive"))
      (node (ref "C47") (pin "P$2") (pinfunction "2_P$2") (pintype "passive"))
      (node (ref "C49") (pin "P$2") (pinfunction "2_P$2") (pintype "passive"))
      (node (ref "C5") (pin "P$2") (pinfunction "2_P$2") (pintype "passive"))
      (node (ref "C52") (pin "P$2") (pinfunction "2_P$2") (pintype "passive"))
      (node (ref "C53") (pin "P$2") (pinfunction "2_P$2") (pintype "passive"))
      (node (ref "C6") (pin "P$2") (pinfunction "2_P$2") (pintype "passive"))
      (node (ref "C7") (pin "P$2") (pinfunction "2_P$2") (pintype "passive"))
      (node (ref "C8") (pin "P$2") (pinfunction "2_P$2") (pintype "passive"))
      (node (ref "D1") (pin "A") (pinfunction "A_A") (pintype "passive"))
      (node (ref "D2") (pin "A") (pinfunction "A_A") (pintype "passive"))
      (node (ref "D3") (pin "C") (pinfunction "P$2_C") (pintype "bidirectional"))
      (node (ref "D4") (pin "A") (pinfunction "A_A") (pintype "passive"))
      (node (ref "GND1") (pin "TP") (pinfunction "TP_TP") (pintype "input"))
      (node (ref "GND2") (pin "TP") (pinfunction "TP_TP") (pintype "input"))
      (node (ref "J$1") (pin "GND@0") (pinfunction "GND_GND@0") (pintype "bidirectional"))
      (node (ref "J$1") (pin "GND@1") (pinfunction "GND_GND@1") (pintype "bidirectional"))
      (node (ref "J$1") (pin "GND@2") (pinfunction "GND_GND@2") (pintype "bidirectional"))
      (node (ref "J$1") (pin "GND@3") (pinfunction "GND_GND@3") (pintype "bidirectional"))
      (node (ref "JLINK") (pin "1") (pinfunction "1_1") (pintype "passive"))
      (node (ref "JP1") (pin "8") (pinfunction "8_8") (pintype "bidirectional"))
      (node (ref "L14") (pin "P$1") (pinfunction "1_P$1") (pintype "passive"))
      (node (ref "Q1") (pin "1") (pinfunction "G_1") (pintype "passive"))
      (node (ref "R12") (pin "P$1") (pinfunction "P$1_P$1") (pintype "passive"))
      (node (ref "R18") (pin "P$1") (pinfunction "P$1_P$1") (pintype "passive"))
      (node (ref "R23") (pin "P$2") (pinfunction "P$2_P$2") (pintype "passive"))
      (node (ref "R24") (pin "P$1") (pinfunction "P$1_P$1") (pintype "passive"))
      (node (ref "R4") (pin "P$1") (pinfunction "P$1_P$1") (pintype "passive"))
      (node (ref "R7") (pin "P$2") (pinfunction "P$2_P$2") (pintype "passive"))
      (node (ref "S1") (pin "P$2") (pinfunction "S2_P$2") (pintype "bidirectional"))
      (node (ref "SWDIO1") (pin "TP") (pinfunction "TP_TP") (pintype "input"))
      (node (ref "SWDIO2") (pin "TP") (pinfunction "TP_TP") (pintype "input"))
      (node (ref "SWDIO3") (pin "TP") (pinfunction "TP_TP") (pintype "input"))
      (node (ref "SWDIO4") (pin "TP") (pinfunction "TP_TP") (pintype "input"))
      (node (ref "SWDIO5") (pin "TP") (pinfunction "TP_TP") (pintype "input"))
      (node (ref "SWDIO6") (pin "TP") (pinfunction "TP_TP") (pintype "input"))
      (node (ref "U1") (pin "2") (pinfunction "GND_2") (pintype "bidirectional"))
      (node (ref "U11") (pin "18") (pinfunction "GNDX_18") (pintype "bidirectional"))
      (node (ref "U11") (pin "3") (pinfunction "RXN_3") (pintype "input"))
      (node (ref "U11") (pin "5") (pinfunction "NC_5") (pintype "bidirectional"))
      (node (ref "U11") (pin "EXP") (pinfunction "PAD_EXP") (pintype "bidirectional"))
      (node (ref "U12") (pin "18") (pinfunction "GNDX_18") (pintype "bidirectional"))
      (node (ref "U12") (pin "3") (pinfunction "RXN_3") (pintype "input"))
      (node (ref "U12") (pin "5") (pinfunction "NC_5") (pintype "bidirectional"))
      (node (ref "U12") (pin "EXP") (pinfunction "PAD_EXP") (pintype "bidirectional"))
      (node (ref "U13") (pin "16") (pinfunction "VSS_16") (pintype "bidirectional"))
      (node (ref "U13") (pin "32") (pinfunction "VSS_32") (pintype "bidirectional"))
      (node (ref "U13") (pin "EXP") (pinfunction "PAD_EXP") (pintype "bidirectional"))
      (node (ref "U14") (pin "1") (pinfunction "S_1") (pintype "bidirectional"))
      (node (ref "U14") (pin "4") (pinfunction "S_4") (pintype "bidirectional"))
      (node (ref "U15") (pin "P$1") (pinfunction "GND_P$1") (pintype "bidirectional"))
      (node (ref "U15") (pin "P$10") (pinfunction "GND_P$10") (pintype "bidirectional"))
      (node (ref "U15") (pin "P$12") (pinfunction "GND_P$12") (pintype "bidirectional"))
      (node (ref "U15") (pin "P$13") (pinfunction "GND_P$13") (pintype "bidirectional"))
      (node (ref "U15") (pin "P$3") (pinfunction "GND_P$3") (pintype "bidirectional"))
      (node (ref "U15") (pin "P$4") (pinfunction "GND_P$4") (pintype "bidirectional"))
      (node (ref "U15") (pin "P$6") (pinfunction "GND_P$6") (pintype "bidirectional"))
      (node (ref "U17") (pin "1") (pinfunction "S_1") (pintype "bidirectional"))
      (node (ref "U17") (pin "4") (pinfunction "S_4") (pintype "bidirectional"))
      (node (ref "U2") (pin "P$1") (pinfunction "GND_P$1") (pintype "bidirectional"))
      (node (ref "U2") (pin "P$10") (pinfunction "GND_P$10") (pintype "bidirectional"))
      (node (ref "U2") (pin "P$12") (pinfunction "GND_P$12") (pintype "bidirectional"))
      (node (ref "U3") (pin "P$4") (pinfunction "GND_P$4") (pintype "bidirectional"))
      (node (ref "U3") (pin "P$7") (pinfunction "GND_P$7") (pintype "bidirectional"))
      (node (ref "U4") (pin "4") (pinfunction "S_4") (pintype "bidirectional"))
      (node (ref "U5") (pin "2") (pinfunction "GND_2") (pintype "bidirectional"))
      (node (ref "U5") (pin "4") (pinfunction "GND_4") (pintype "bidirectional"))
      (node (ref "U5") (pin "5") (pinfunction "GND_5") (pintype "bidirectional"))
      (node (ref "U7") (pin "2") (pinfunction "S_2") (pintype "passive"))
      (node (ref "U7") (pin "2@1") (pinfunction "PAD_2@1") (pintype "bidirectional"))
      (node (ref "U9") (pin "P$3") (pinfunction "GND_P$3") (pintype "bidirectional"))
      (node (ref "X1") (pin "2") (pinfunction "G2_2") (pintype "power_in"))
      (node (ref "X1") (pin "4") (pinfunction "G1_4") (pintype "power_in"))
      (node (ref "X2") (pin "2") (pinfunction "G2_2") (pintype "power_in"))
      (node (ref "X2") (pin "4") (pinfunction "G1_4") (pintype "power_in"))
      (node (ref "Z2") (pin "P$1") (pinfunction "P$1_P$1") (pintype "passive"))
      (node (ref "Z3") (pin "P$1") (pinfunction "P$1_P$1") (pintype "passive"))
    )
    (net (code "6") (name "GPS_1PPS") (class "Default")
      (node (ref "U2") (pin "P$4") (pinfunction "1PPS_P$4") (pintype "bidirectional"))
      (node (ref "U4") (pin "5") (pinfunction "G_5") (pintype "bidirectional"))
    )
    (net (code "7") (name "GPS_EN") (class "Default")
      (node (ref "R3") (pin "P$2") (pinfunction "P$2_P$2") (pintype "passive"))
      (node (ref "R6") (pin "P$2") (pinfunction "P$2_P$2") (pintype "passive"))
      (node (ref "R7") (pin "P$1") (pinfunction "P$1_P$1") (pintype "passive"))
      (node (ref "U13") (pin "2") (pinfunction "OSC_IN/PC14_2") (pintype "bidirectional"))
      (node (ref "U4") (pin "2") (pinfunction "G_2") (pintype "bidirectional"))
    )
    (net (code "8") (name "GPS_STATUS") (class "Default")
      (node (ref "U13") (pin "21") (pinfunction "PA11_21") (pintype "bidirectional"))
      (node (ref "U14") (pin "5") (pinfunction "G_5") (pintype "bidirectional"))
    )
    (net (code "9") (name "GPS_UART_TX") (class "Default")
      (node (ref "R3") (pin "P$1") (pinfunction "P$1_P$1") (pintype "passive"))
      (node (ref "U2") (pin "P$2") (pinfunction "TX_P$2") (pintype "bidirectional"))
      (node (ref "U4") (pin "1") (pinfunction "S_1") (pintype "bidirectional"))
    )
    (net (code "10") (name "HOST_GPS_STATUS") (class "Default")
      (node (ref "JP1") (pin "4") (pinfunction "4_4") (pintype "bidirectional"))
      (node (ref "R14") (pin "P$2") (pinfunction "P$2_P$2") (pintype "passive"))
      (node (ref "U9") (pin "P$2") (pinfunction "C2_P$2") (pintype "bidirectional"))
    )
    (net (code "11") (name "HOST_RX_STATUS") (class "Default")
      (node (ref "JP1") (pin "6") (pinfunction "6_6") (pintype "bidirectional"))
      (node (ref "R15") (pin "P$2") (pinfunction "P$2_P$2") (pintype "passive"))
      (node (ref "U9") (pin "P$7") (pinfunction "C6_P$7") (pintype "bidirectional"))
    )
    (net (code "12") (name "HOST_TX_OFF") (class "Default")
      (node (ref "JP1") (pin "2") (pinfunction "2_2") (pintype "bidirectional"))
      (node (ref "R18") (pin "P$2") (pinfunction "P$2_P$2") (pintype "passive"))
      (node (ref "U17") (pin "2") (pinfunction "G_2") (pintype "bidirectional"))
      (node (ref "U9") (pin "P$1") (pinfunction "C1_P$1") (pintype "bidirectional"))
    )
    (net (code "13") (name "HOST_TX_STATUS") (class "Default")
      (node (ref "JP1") (pin "7") (pinfunction "7_7") (pintype "bidirectional"))
      (node (ref "R17") (pin "P$2") (pinfunction "P$2_P$2") (pintype "passive"))
      (node (ref "U9") (pin "P$6") (pinfunction "C5_P$6") (pintype "bidirectional"))
    )
    (net (code "14") (name "HOST_UART_RX") (class "Default")
      (node (ref "JP1") (pin "5") (pinfunction "5_5") (pintype "bidirectional"))
      (node (ref "R13") (pin "P$2") (pinfunction "P$2_P$2") (pintype "passive"))
      (node (ref "U9") (pin "P$8") (pinfunction "C7_P$8") (pintype "bidirectional"))
    )
    (net (code "15") (name "HOST_UART_TX") (class "Default")
      (node (ref "JP1") (pin "3") (pinfunction "3_3") (pintype "bidirectional"))
      (node (ref "R2") (pin "P$2") (pinfunction "P$2_P$2") (pintype "passive"))
      (node (ref "U9") (pin "P$9") (pinfunction "C8_P$9") (pintype "bidirectional"))
    )
    (net (code "16") (name "MCU_GPS_1PPS") (class "Default")
      (node (ref "R6") (pin "P$1") (pinfunction "P$1_P$1") (pintype "passive"))
      (node (ref "U13") (pin "8") (pinfunction "PA2_8") (pintype "bidirectional"))
      (node (ref "U4") (pin "3") (pinfunction "D_3") (pintype "bidirectional"))
    )
    (net (code "17") (name "MCU_GPS_UART_RX") (class "Default")
      (node (ref "R16") (pin "P$1") (pinfunction "P$1_P$1") (pintype "passive"))
      (node (ref "U13") (pin "9") (pinfunction "PA3_9") (pintype "bidirectional"))
      (node (ref "U4") (pin "6") (pinfunction "D_6") (pintype "bidirectional"))
    )
    (net (code "18") (name "MCU_TX_OFF") (class "Default")
      (node (ref "U13") (pin "22") (pinfunction "PA12_22") (pintype "bidirectional"))
      (node (ref "U17") (pin "6") (pinfunction "D_6") (pintype "bidirectional"))
    )
    (net (code "19") (name "MCU_UART_RX") (class "Default")
      (node (ref "D1") (pin "C") (pinfunction "C_C") (pintype "passive"))
      (node (ref "R2") (pin "P$1") (pinfunction "P$1_P$1") (pintype "passive"))
      (node (ref "RX") (pin "TP") (pinfunction "TP_TP") (pintype "input"))
      (node (ref "U13") (pin "20") (pinfunction "PA10_20") (pintype "bidirectional"))
    )
    (net (code "20") (name "MCU_UART_TX") (class "Default")
      (node (ref "D2") (pin "C") (pinfunction "C_C") (pintype "passive"))
      (node (ref "R13") (pin "P$1") (pinfunction "P$1_P$1") (pintype "passive"))
      (node (ref "TX") (pin "TP") (pinfunction "TP_TP") (pintype "input"))
      (node (ref "U13") (pin "19") (pinfunction "PA9_19") (pintype "bidirectional"))
    )
    (net (code "21") (name "MISO") (class "Default")
      (node (ref "U11") (pin "13") (pinfunction "SDO_13") (pintype "output"))
      (node (ref "U12") (pin "13") (pinfunction "SDO_13") (pintype "output"))
      (node (ref "U13") (pin "12") (pinfunction "PA6_12") (pintype "bidirectional"))
    )
    (net (code "22") (name "MOSI") (class "Default")
      (node (ref "U11") (pin "14") (pinfunction "SDI_14") (pintype "input"))
      (node (ref "U12") (pin "14") (pinfunction "SDI_14") (pintype "input"))
      (node (ref "U13") (pin "13") (pinfunction "PA7_13") (pintype "bidirectional"))
    )
    (net (code "23") (name "NRST") (class "Default")
      (node (ref "JLINK") (pin "2") (pinfunction "2_2") (pintype "passive"))
      (node (ref "NRST") (pin "TP") (pinfunction "TP_TP") (pintype "input"))
      (node (ref "S1") (pin "P$1") (pinfunction "S1_P$1") (pintype "bidirectional"))
      (node (ref "U13") (pin "4") (pinfunction "NRST_4") (pintype "bidirectional"))
    )
    (net (code "24") (name "Net-(C1-1)") (class "Default")
      (node (ref "C1") (pin "P$1") (pinfunction "1_P$1") (pintype "passive"))
      (node (ref "C43") (pin "P$1") (pinfunction "1_P$1") (pintype "passive"))
      (node (ref "L2") (pin "P$2") (pinfunction "2_P$2") (pintype "passive"))
      (node (ref "U1") (pin "4") (pinfunction "EN_4") (pintype "bidirectional"))
      (node (ref "U1") (pin "5") (pinfunction "IN_5") (pintype "bidirectional"))
    )
    (net (code "25") (name "Net-(C2-1)") (class "Default")
      (node (ref "C2") (pin "P$1") (pinfunction "1_P$1") (pintype "passive"))
      (node (ref "U1") (pin "1") (pinfunction "BS_1") (pintype "bidirectional"))
    )
    (net (code "26") (name "Net-(C2-2)") (class "Default")
      (node (ref "C2") (pin "P$2") (pinfunction "2_P$2") (pintype "passive"))
      (node (ref "D4") (pin "C") (pinfunction "C_C") (pintype "passive"))
      (node (ref "L12") (pin "P$1") (pinfunction "1_P$1") (pintype "passive"))
      (node (ref "U1") (pin "6") (pinfunction "SW_6") (pintype "bidirectional"))
    )
    (net (code "27") (name "Net-(C9-1)") (class "Default")
      (node (ref "C9") (pin "P$1") (pinfunction "1_P$1") (pintype "passive"))
      (node (ref "L8") (pin "P$2") (pinfunction "2_P$2") (pintype "passive"))
    )
    (net (code "28") (name "Net-(C10-1)") (class "Default")
      (node (ref "C10") (pin "P$1") (pinfunction "1_P$1") (pintype "passive"))
      (node (ref "C8") (pin "P$1") (pinfunction "1_P$1") (pintype "passive"))
      (node (ref "C9") (pin "P$2") (pinfunction "2_P$2") (pintype "passive"))
      (node (ref "L14") (pin "P$2") (pinfunction "2_P$2") (pintype "passive"))
    )
    (net (code "29") (name "Net-(C10-2)") (class "Default")
      (node (ref "C10") (pin "P$2") (pinfunction "2_P$2") (pintype "passive"))
      (node (ref "L13") (pin "P$1") (pinfunction "1_P$1") (pintype "passive"))
    )
    (net (code "30") (name "Net-(C12-1)") (class "Default")
      (node (ref "C12") (pin "P$1") (pinfunction "1_P$1") (pintype "passive"))
      (node (ref "L13") (pin "P$2") (pinfunction "2_P$2") (pintype "passive"))
    )
    (net (code "31") (name "Net-(C12-2)") (class "Default")
      (node (ref "C12") (pin "P$2") (pinfunction "2_P$2") (pintype "passive"))
      (node (ref "U5") (pin "6") (pinfunction "IN_6") (pintype "bidirectional"))
    )
    (net (code "32") (name "Net-(C13-1)") (class "Default")
      (node (ref "C13") (pin "P$1") (pinfunction "1_P$1") (pintype "passive"))
      (node (ref "R10") (pin "P$2") (pinfunction "P$2_P$2") (pintype "passive"))
      (node (ref "U5") (pin "1") (pinfunction "VCC_1") (pintype "bidirectional"))
    )
    (net (code "33") (name "Net-(C18-1)") (class "Default")
      (node (ref "C18") (pin "P$1") (pinfunction "1_P$1") (pintype "passive"))
      (node (ref "U5") (pin "3") (pinfunction "OUT_3") (pintype "bidirectional"))
    )
    (net (code "34") (name "Net-(C21-1)") (class "Default")
      (node (ref "C21") (pin "P$1") (pinfunction "1_P$1") (pintype "passive"))
      (node (ref "L5") (pin "P$1") (pinfunction "1_P$1") (pintype "passive"))
      (node (ref "R22") (pin "P$1") (pinfunction "P$1_P$1") (pintype "passive"))
    )
    (net (code "35") (name "Net-(C22-1)") (class "Default")
      (node (ref "C22") (pin "P$1") (pinfunction "1_P$1") (pintype "passive"))
      (node (ref "L5") (pin "P$2") (pinfunction "2_P$2") (pintype "passive"))
      (node (ref "U11") (pin "4") (pinfunction "TX_4") (pintype "output"))
    )
    (net (code "36") (name "Net-(C22-2)") (class "Default")
      (node (ref "C22") (pin "P$2") (pinfunction "2_P$2") (pintype "passive"))
      (node (ref "L1") (pin "P$1") (pinfunction "1_P$1") (pintype "passive"))
    )
    (net (code "37") (name "Net-(C23-1)") (class "Default")
      (node (ref "C23") (pin "P$1") (pinfunction "1_P$1") (pintype "passive"))
      (node (ref "L1") (pin "P$2") (pinfunction "2_P$2") (pintype "passive"))
      (node (ref "L6") (pin "P$1") (pinfunction "1_P$1") (pintype "passive"))
    )
    (net (code "38") (name "Net-(C24-1)") (class "Default")
      (node (ref "C24") (pin "P$1") (pinfunction "1_P$1") (pintype "passive"))
      (node (ref "L6") (pin "P$2") (pinfunction "2_P$2") (pintype "passive"))
      (node (ref "L7") (pin "P$1") (pinfunction "1_P$1") (pintype "passive"))
    )
    (net (code "39") (name "Net-(C25-1)") (class "Default")
      (node (ref "C25") (pin "P$1") (pinfunction "1_P$1") (pintype "passive"))
      (node (ref "L11") (pin "P$1") (pinfunction "1_P$1") (pintype "passive"))
      (node (ref "L7") (pin "P$2") (pinfunction "2_P$2") (pintype "passive"))
    )
    (net (code "40") (name "Net-(C29-2)") (class "Default")
      (node (ref "C29") (pin "P$2") (pinfunction "2_P$2") (pintype "passive"))
      (node (ref "C30") (pin "P$1") (pinfunction "1_P$1") (pintype "passive"))
      (node (ref "L3") (pin "P$1") (pinfunction "1_P$1") (pintype "passive"))
    )
    (net (code "41") (name "Net-(C36-1)") (class "Default")
      (node (ref "C36") (pin "P$1") (pinfunction "1_P$1") (pintype "passive"))
      (node (ref "L10") (pin "P$1") (pinfunction "1_P$1") (pintype "passive"))
      (node (ref "L9") (pin "P$2") (pinfunction "2_P$2") (pintype "passive"))
    )
    (net (code "42") (name "Net-(C37-1)") (class "Default")
      (node (ref "C37") (pin "P$1") (pinfunction "1_P$1") (pintype "passive"))
      (node (ref "C39") (pin "P$1") (pinfunction "1_P$1") (pintype "passive"))
      (node (ref "L4") (pin "P$2") (pinfunction "2_P$2") (pintype "passive"))
      (node (ref "L9") (pin "P$1") (pinfunction "1_P$1") (pintype "passive"))
      (node (ref "U7") (pin "3") (pinfunction "D_3") (pintype "passive"))
    )
    (net (code "43") (name "Net-(C42-1)") (class "Default")
      (node (ref "C42") (pin "P$1") (pinfunction "1_P$1") (pintype "passive"))
      (node (ref "C52") (pin "P$1") (pinfunction "1_P$1") (pintype "passive"))
      (node (ref "L10") (pin "P$2") (pinfunction "2_P$2") (pintype "passive"))
      (node (ref "L23") (pin "P$1") (pinfunction "1_P$1") (pintype "passive"))
    )
    (net (code "44") (name "Net-(C44-1)") (class "Default")
      (node (ref "C44") (pin "P$1") (pinfunction "1_P$1") (pintype "passive"))
      (node (ref "C53") (pin "P$1") (pinfunction "1_P$1") (pintype "passive"))
      (node (ref "L23") (pin "P$2") (pinfunction "2_P$2") (pintype "passive"))
    )
    (net (code "45") (name "Net-(J$1-SIGNAL)") (class "Default")
      (node (ref "J$1") (pin "SIG") (pinfunction "SIGNAL_SIG") (pintype "bidirectional"))
      (node (ref "RF") (pin "TP") (pinfunction "TP_TP") (pintype "input"))
      (node (ref "U15") (pin "P$2") (pinfunction "RF1_P$2") (pintype "bidirectional"))
    )
    (net (code "46") (name "Net-(L17-1)") (class "Default")
      (node (ref "L17") (pin "P$1") (pinfunction "1_P$1") (pintype "passive"))
      (node (ref "L3") (pin "P$2") (pinfunction "2_P$2") (pintype "passive"))
      (node (ref "U7") (pin "1") (pinfunction "G_1") (pintype "passive"))
    )
    (net (code "47") (name "Net-(U1-FB)") (class "Default")
      (node (ref "R21") (pin "P$1") (pinfunction "P$1_P$1") (pintype "passive"))
      (node (ref "R24") (pin "P$2") (pinfunction "P$2_P$2") (pintype "passive"))
      (node (ref "U1") (pin "3") (pinfunction "FB_3") (pintype "bidirectional"))
    )
    (net (code "48") (name "Net-(U2-RFIN)") (class "Default")
      (node (ref "U2") (pin "P$11") (pinfunction "RFIN_P$11") (pintype "bidirectional"))
      (node (ref "Z1") (pin "P$2") (pinfunction "P$2_P$2") (pintype "passive"))
      (node (ref "Z3") (pin "P$2") (pinfunction "P$2_P$2") (pintype "passive"))
    )
    (net (code "49") (name "Net-(U3-ADJ)") (class "Default")
      (node (ref "R4") (pin "P$2") (pinfunction "P$2_P$2") (pintype "passive"))
      (node (ref "R5") (pin "P$1") (pinfunction "P$1_P$1") (pintype "passive"))
      (node (ref "U3") (pin "P$2") (pinfunction "ADJ_P$2") (pintype "bidirectional"))
    )
    (net (code "50") (name "Net-(U10-RF)") (class "Default")
      (node (ref "U10") (pin "P$1") (pinfunction "RF_P$1") (pintype "bidirectional"))
      (node (ref "Z1") (pin "P$1") (pinfunction "P$1_P$1") (pintype "passive"))
      (node (ref "Z2") (pin "P$2") (pinfunction "P$2_P$2") (pintype "passive"))
    )
    (net (code "51") (name "Net-(U11-XIN)") (class "Default")
      (node (ref "U11") (pin "17") (pinfunction "XIN_17") (pintype "input"))
      (node (ref "X1") (pin "3") (pinfunction "X2_3") (pintype "bidirectional"))
    )
    (net (code "52") (name "Net-(U11-XOUT)") (class "Default")
      (node (ref "U11") (pin "16") (pinfunction "XOUT_16") (pintype "bidirectional"))
      (node (ref "X1") (pin "1") (pinfunction "X1_1") (pintype "bidirectional"))
    )
    (net (code "53") (name "Net-(U12-XIN)") (class "Default")
      (node (ref "U12") (pin "17") (pinfunction "XIN_17") (pintype "input"))
      (node (ref "X2") (pin "3") (pinfunction "X2_3") (pintype "bidirectional"))
    )
    (net (code "54") (name "Net-(U12-XOUT)") (class "Default")
      (node (ref "U12") (pin "16") (pinfunction "XOUT_16") (pintype "bidirectional"))
      (node (ref "X2") (pin "1") (pinfunction "X1_1") (pintype "bidirectional"))
    )
    (net (code "55") (name "Net-(U14A-D)") (class "Default")
      (node (ref "R14") (pin "P$1") (pinfunction "P$1_P$1") (pintype "passive"))
      (node (ref "U14") (pin "3") (pinfunction "D_3") (pintype "bidirectional"))
    )
    (net (code "56") (name "Net-(U14B-D)") (class "Default")
      (node (ref "R15") (pin "P$1") (pinfunction "P$1_P$1") (pintype "passive"))
      (node (ref "U14") (pin "6") (pinfunction "D_6") (pintype "bidirectional"))
    )
    (net (code "57") (name "Net-(U15-CTRL)") (class "Default")
      (node (ref "D6") (pin "C") (pinfunction "C_C") (pintype "bidirectional"))
      (node (ref "U15") (pin "P$7") (pinfunction "CTRL_P$7") (pintype "bidirectional"))
    )
    (net (code "58") (name "Net-(U17A-D)") (class "Default")
      (node (ref "R17") (pin "P$1") (pinfunction "P$1_P$1") (pintype "passive"))
      (node (ref "U17") (pin "3") (pinfunction "D_3") (pintype "bidirectional"))
    )
    (net (code "59") (name "PA_GATE_BIAS") (class "Default")
      (node (ref "C11") (pin "P$1") (pinfunction "1_P$1") (pintype "passive"))
      (node (ref "L17") (pin "P$2") (pinfunction "2_P$2") (pintype "passive"))
      (node (ref "R11") (pin "P$1") (pinfunction "P$1_P$1") (pintype "passive"))
      (node (ref "R12") (pin "P$2") (pinfunction "P$2_P$2") (pintype "passive"))
    )
    (net (code "60") (name "PA_IN") (class "Default")
      (node (ref "C29") (pin "P$1") (pinfunction "1_P$1") (pintype "passive"))
      (node (ref "L11") (pin "P$2") (pinfunction "2_P$2") (pintype "passive"))
    )
    (net (code "61") (name "PA_OUT") (class "Default")
      (node (ref "C44") (pin "P$2") (pinfunction "2_P$2") (pintype "passive"))
      (node (ref "U15") (pin "P$5") (pinfunction "RF3_P$5") (pintype "bidirectional"))
    )
    (net (code "62") (name "RFSW_EN") (class "Default")
      (node (ref "D5") (pin "C") (pinfunction "C_C") (pintype "bidirectional"))
      (node (ref "U15") (pin "P$8") (pinfunction "EN_P$8") (pintype "bidirectional"))
    )
    (net (code "63") (name "RF_IN") (class "Default")
      (node (ref "L8") (pin "P$1") (pinfunction "1_P$1") (pintype "passive"))
      (node (ref "U15") (pin "P$11") (pinfunction "RF2_P$11") (pintype "bidirectional"))
    )
    (net (code "64") (name "RX_EN") (class "Default")
      (node (ref "D6") (pin "A") (pinfunction "A_A") (pintype "bidirectional"))
      (node (ref "R10") (pin "P$1") (pinfunction "P$1_P$1") (pintype "passive"))
      (node (ref "U13") (pin "29") (pinfunction "PB6_29") (pintype "bidirectional"))
      (node (ref "V_LNA") (pin "TP") (pinfunction "TP_TP") (pintype "input"))
    )
    (net (code "65") (name "RX_IC_CLK") (class "Default")
      (node (ref "U12") (pin "20") (pinfunction "GPIO3_20") (pintype "bidirectional"))
      (node (ref "U13") (pin "26") (pinfunction "PB3_26") (pintype "bidirectional"))
    )
    (net (code "66") (name "RX_IC_DATA") (class "Default")
      (node (ref "U12") (pin "10") (pinfunction "GPIO1_10") (pintype "bidirectional"))
      (node (ref "U13") (pin "27") (pinfunction "PB4_27") (pintype "bidirectional"))
    )
    (net (code "67") (name "RX_IN") (class "Default")
      (node (ref "C18") (pin "P$2") (pinfunction "2_P$2") (pintype "passive"))
      (node (ref "U11") (pin "2") (pinfunction "RXP_2") (pintype "input"))
      (node (ref "U12") (pin "2") (pinfunction "RXP_2") (pintype "input"))
    )
    (net (code "68") (name "RX_STATUS") (class "Default")
      (node (ref "U13") (pin "7") (pinfunction "PA1_7") (pintype "bidirectional"))
      (node (ref "U14") (pin "2") (pinfunction "G_2") (pintype "bidirectional"))
    )
    (net (code "69") (name "SCK") (class "Default")
      (node (ref "U11") (pin "12") (pinfunction "SCLK_12") (pintype "input"))
      (node (ref "U12") (pin "12") (pinfunction "SCLK_12") (pintype "input"))
      (node (ref "U13") (pin "11") (pinfunction "PA5_11") (pintype "bidirectional"))
    )
    (net (code "70") (name "SDN1") (class "Default")
      (node (ref "U11") (pin "1") (pinfunction "SDN_1") (pintype "input"))
      (node (ref "U13") (pin "14") (pinfunction "PB0_14") (pintype "bidirectional"))
    )
    (net (code "71") (name "SDN2") (class "Default")
      (node (ref "U12") (pin "1") (pinfunction "SDN_1") (pintype "input"))
      (node (ref "U13") (pin "25") (pinfunction "PA15_25") (pintype "bidirectional"))
    )
    (net (code "72") (name "SWCLK") (class "Default")
      (node (ref "JLINK") (pin "3") (pinfunction "3_3") (pintype "passive"))
      (node (ref "SWCLK") (pin "TP") (pinfunction "TP_TP") (pintype "input"))
      (node (ref "U13") (pin "24") (pinfunction "PA14_24") (pintype "bidirectional"))
    )
    (net (code "73") (name "SWDIO") (class "Default")
      (node (ref "JLINK") (pin "4") (pinfunction "4_4") (pintype "passive"))
      (node (ref "SWDIO") (pin "TP") (pinfunction "TP_TP") (pintype "input"))
      (node (ref "U13") (pin "23") (pinfunction "PA13_23") (pintype "bidirectional"))
    )
    (net (code "74") (name "TRX_IC_CLOCK") (class "Default")
      (node (ref "U11") (pin "19") (pinfunction "GPIO2_19") (pintype "bidirectional"))
      (node (ref "U13") (pin "3") (pinfunction "OSC_OUT/PC15_3") (pintype "bidirectional"))
    )
    (net (code "75") (name "TRX_IC_DATA") (class "Default")
      (node (ref "U11") (pin "10") (pinfunction "GPIO1_10") (pintype "bidirectional"))
      (node (ref "U13") (pin "15") (pinfunction "PB1_15") (pintype "bidirectional"))
    )
    (net (code "76") (name "TX_STATUS") (class "Default")
      (node (ref "U13") (pin "28") (pinfunction "PB5_28") (pintype "bidirectional"))
      (node (ref "U17") (pin "5") (pinfunction "G_5") (pintype "bidirectional"))
    )
    (net (code "77") (name "V_IN") (class "Default")
      (node (ref "D3") (pin "A") (pinfunction "P$1_A") (pintype "bidirectional"))
      (node (ref "JP1") (pin "1") (pinfunction "1_1") (pintype "bidirectional"))
      (node (ref "Q1") (pin "3") (pinfunction "D_3") (pintype "passive"))
      (node (ref "V_IN") (pin "TP") (pinfunction "TP_TP") (pintype "input"))
    )
    (net (code "78") (name "V_PA") (class "Default")
      (node (ref "C49") (pin "P$1") (pinfunction "1_P$1") (pintype "passive"))
      (node (ref "C7") (pin "P$1") (pinfunction "1_P$1") (pintype "passive"))
      (node (ref "L4") (pin "P$1") (pinfunction "1_P$1") (pintype "passive"))
      (node (ref "R5") (pin "P$2") (pinfunction "P$2_P$2") (pintype "passive"))
      (node (ref "U3") (pin "P$1") (pinfunction "VOUT_P$1") (pintype "bidirectional"))
      (node (ref "V_PA") (pin "TP") (pinfunction "TP_TP") (pintype "input"))
    )
    (net (code "79") (name "V_PA_BIAS") (class "Default")
      (node (ref "R11") (pin "P$2") (pinfunction "P$2_P$2") (pintype "passive"))
      (node (ref "U13") (pin "18") (pinfunction "PA8_18") (pintype "bidirectional"))
    )
    (net (code "80") (name "V_PROT") (class "Default")
      (node (ref "C4") (pin "P$1") (pinfunction "1_P$1") (pintype "passive"))
      (node (ref "C47") (pin "P$1") (pinfunction "1_P$1") (pintype "passive"))
      (node (ref "L2") (pin "P$1") (pinfunction "1_P$1") (pintype "passive"))
      (node (ref "Q1") (pin "2") (pinfunction "S_2") (pintype "passive"))
      (node (ref "U3") (pin "P$5") (pinfunction "EN_P$5") (pintype "bidirectional"))
      (node (ref "U3") (pin "P$6") (pinfunction "VIN_P$6") (pintype "bidirectional"))
    )
    (net (code "81") (name "unconnected-(S1-S1-PadP$4)") (class "Default")
      (node (ref "S1") (pin "P$4") (pinfunction "S1_P$4") (pintype "bidirectional"))
    )
    (net (code "82") (name "unconnected-(S1-S2-PadP$3)") (class "Default")
      (node (ref "S1") (pin "P$3") (pinfunction "S2_P$3") (pintype "bidirectional"))
    )
    (net (code "83") (name "unconnected-(U2-RX-PadP$3)") (class "Default")
      (node (ref "U2") (pin "P$3") (pinfunction "RX_P$3") (pintype "bidirectional"))
    )
    (net (code "84") (name "unconnected-(U3-PG-PadP$3)") (class "Default")
      (node (ref "U3") (pin "P$3") (pinfunction "PG_P$3") (pintype "bidirectional"))
    )
    (net (code "85") (name "unconnected-(U9-C3-PadP$4)") (class "Default")
      (node (ref "U9") (pin "P$4") (pinfunction "C3_P$4") (pintype "bidirectional"))
    )
    (net (code "86") (name "unconnected-(U9-C4-PadP$5)") (class "Default")
      (node (ref "U9") (pin "P$5") (pinfunction "C4_P$5") (pintype "bidirectional"))
    )
    (net (code "87") (name "unconnected-(U10-PAD-PadP$2)") (class "Default")
      (node (ref "U10") (pin "P$2") (pinfunction "PAD_P$2") (pintype "bidirectional"))
    )
    (net (code "88") (name "unconnected-(U11-GPIO0-Pad9)") (class "Default")
      (node (ref "U11") (pin "9") (pinfunction "GPIO0_9") (pintype "bidirectional"))
    )
    (net (code "89") (name "unconnected-(U11-GPIO3-Pad20)") (class "Default")
      (node (ref "U11") (pin "20") (pinfunction "GPIO3_20") (pintype "bidirectional"))
    )
    (net (code "90") (name "unconnected-(U11-NIRQ-Pad11)") (class "Default")
      (node (ref "U11") (pin "11") (pinfunction "NIRQ_11") (pintype "bidirectional"))
    )
    (net (code "91") (name "unconnected-(U11-TXRAMP-Pad7)") (class "Default")
      (node (ref "U11") (pin "7") (pinfunction "TXRAMP_7") (pintype "bidirectional"))
    )
    (net (code "92") (name "unconnected-(U12-GPIO0-Pad9)") (class "Default")
      (node (ref "U12") (pin "9") (pinfunction "GPIO0_9") (pintype "bidirectional"))
    )
    (net (code "93") (name "unconnected-(U12-GPIO2-Pad19)") (class "Default")
      (node (ref "U12") (pin "19") (pinfunction "GPIO2_19") (pintype "bidirectional"))
    )
    (net (code "94") (name "unconnected-(U12-NIRQ-Pad11)") (class "Default")
      (node (ref "U12") (pin "11") (pinfunction "NIRQ_11") (pintype "bidirectional"))
    )
    (net (code "95") (name "unconnected-(U12-TX-Pad4)") (class "Default")
      (node (ref "U12") (pin "4") (pinfunction "TX_4") (pintype "output"))
    )
    (net (code "96") (name "unconnected-(U12-TXRAMP-Pad7)") (class "Default")
      (node (ref "U12") (pin "7") (pinfunction "TXRAMP_7") (pintype "bidirectional"))
    )
    (net (code "97") (name "unconnected-(U13-PB7-Pad30)") (class "Default")
      (node (ref "U13") (pin "30") (pinfunction "PB7_30") (pintype "bidirectional"))
    )
  )
)
